# toyotune_3s.net
KiCad netlist of a schematic drawn in EAGLE
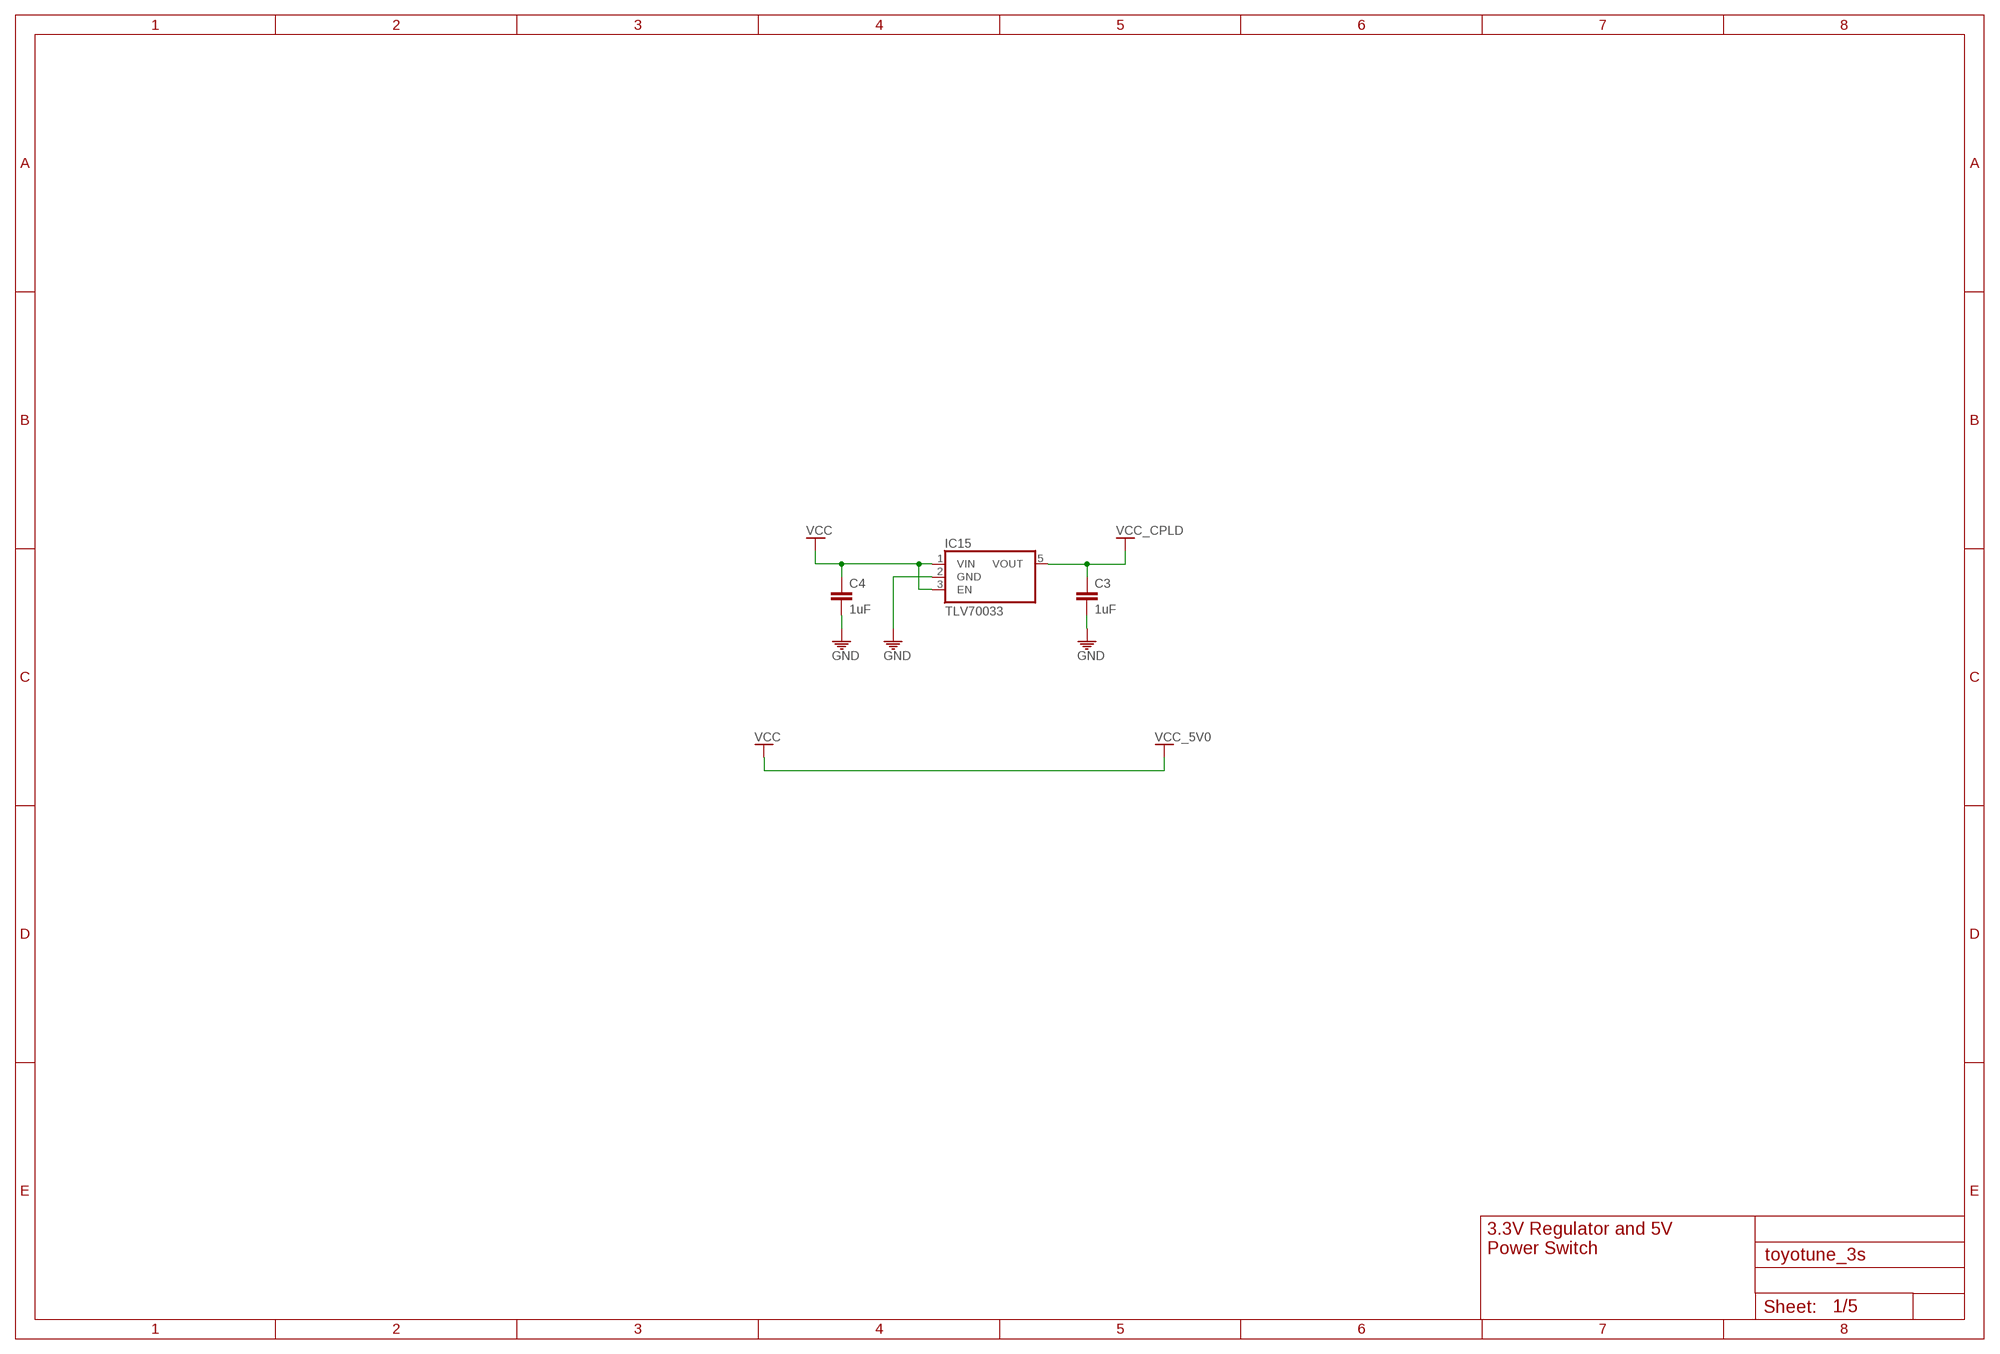
[diagram p0: schematic, sheet 1]
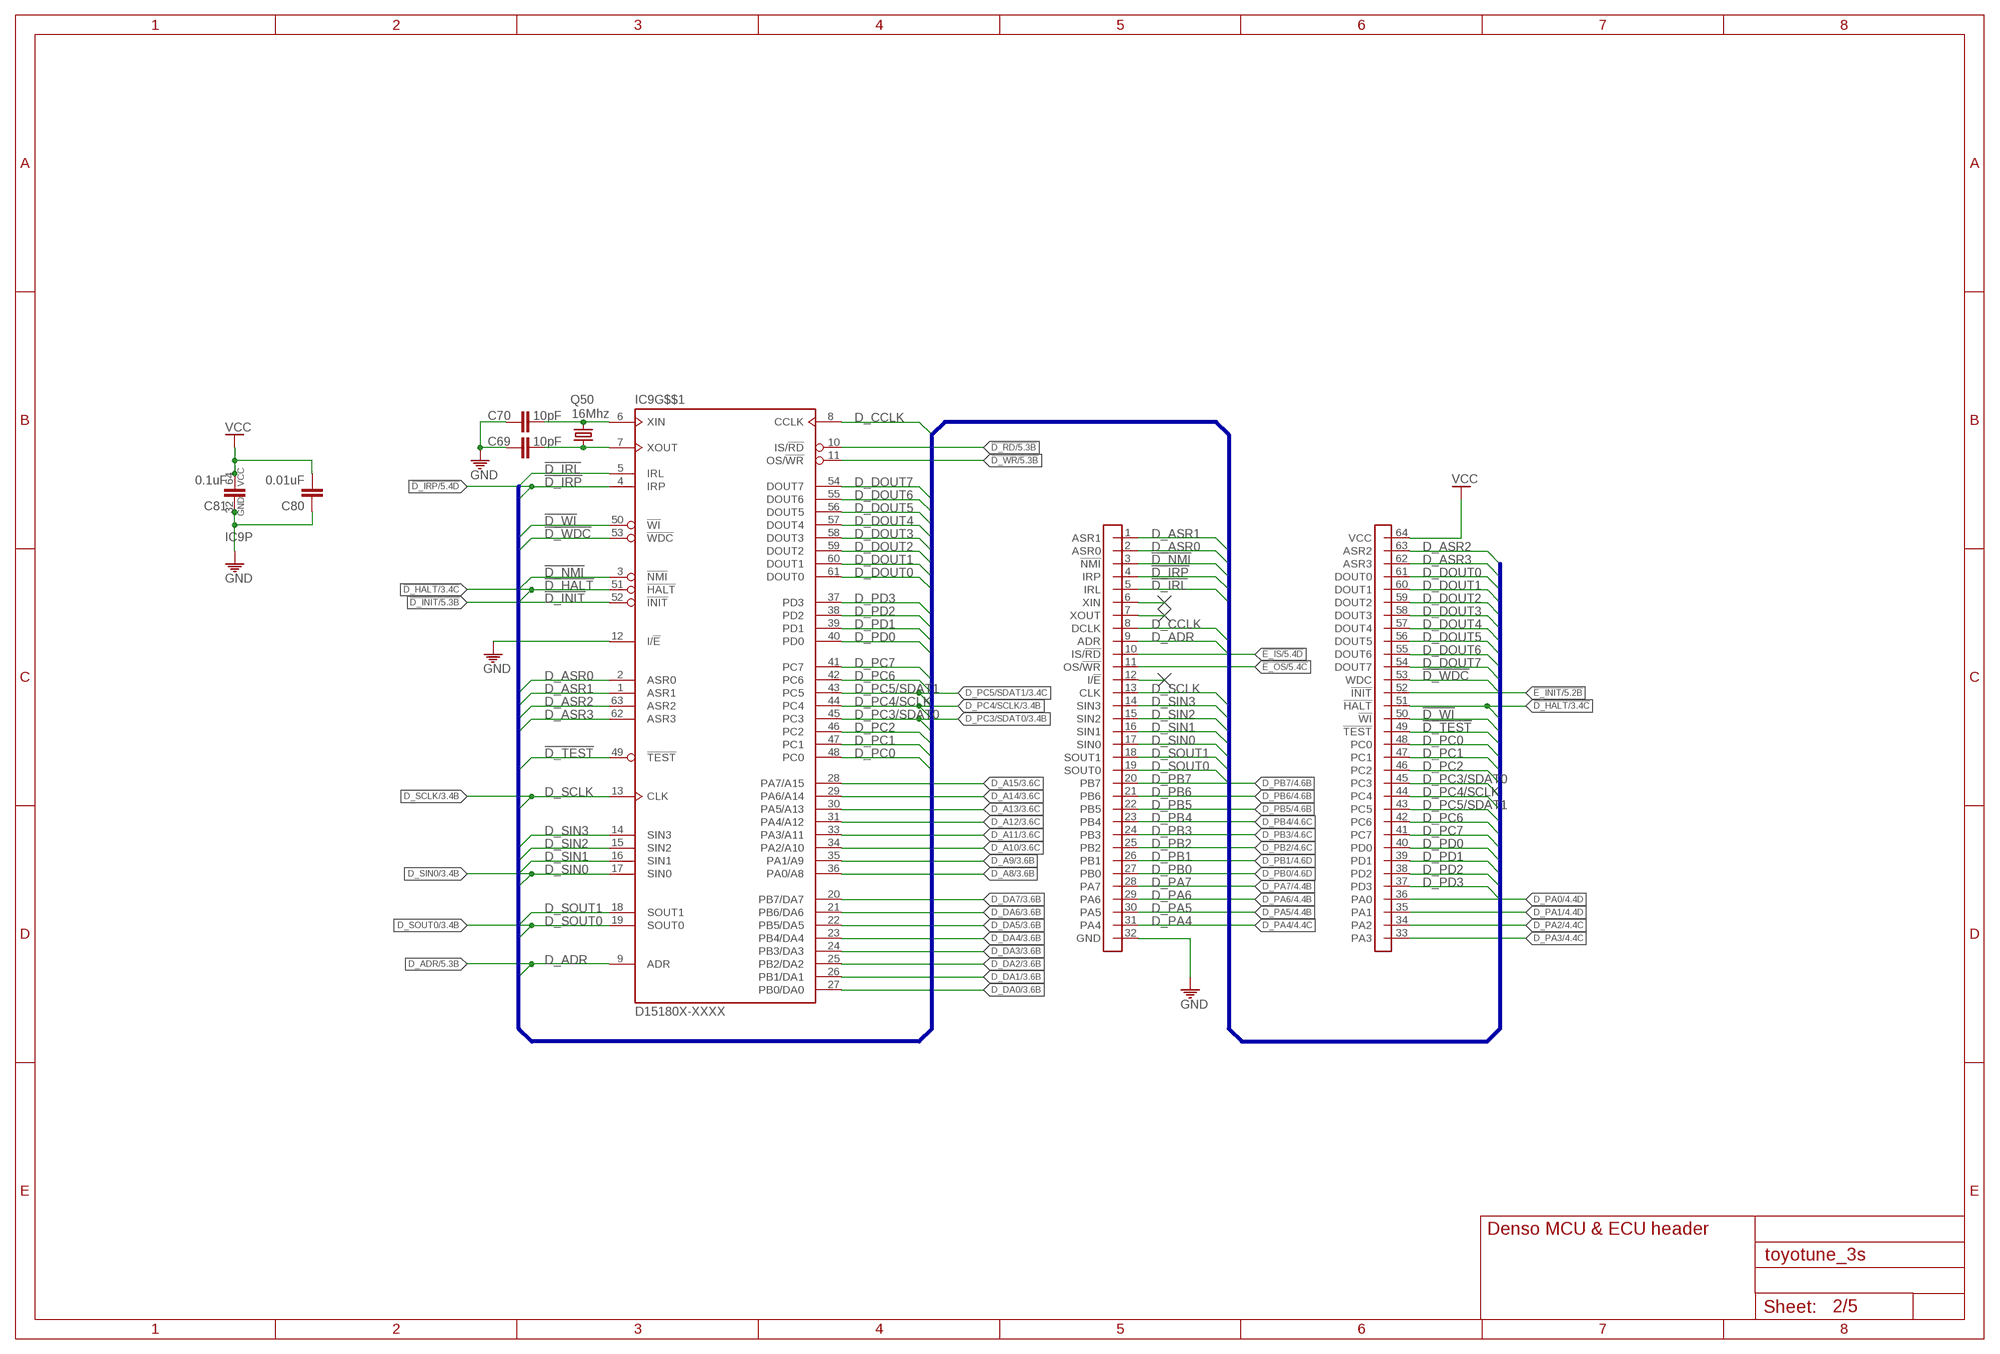
[diagram p1: schematic, sheet 2]
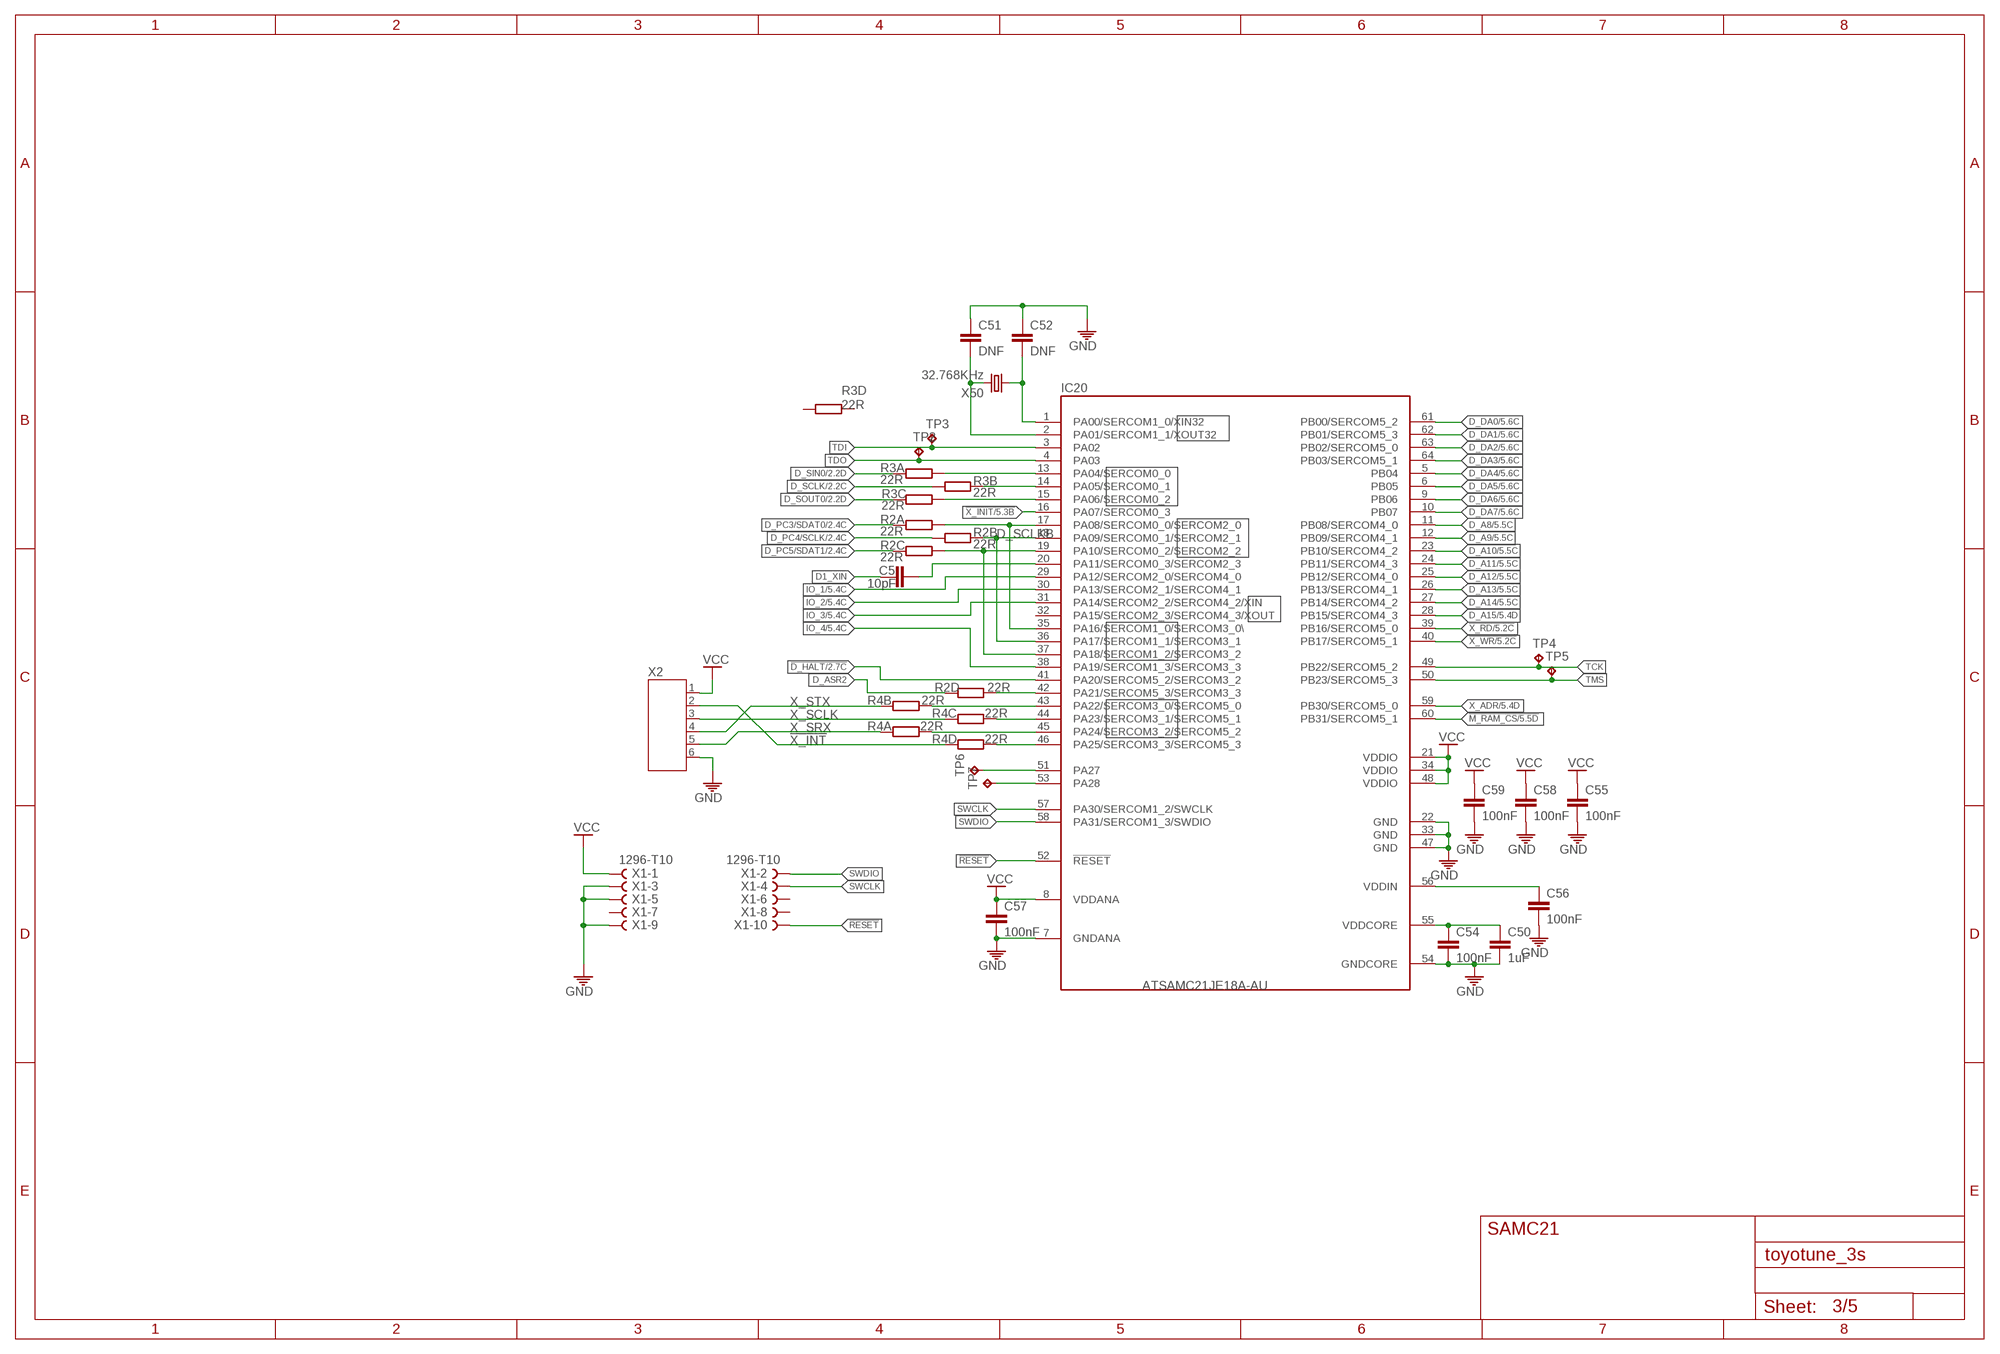
[diagram p2: schematic, sheet 3]
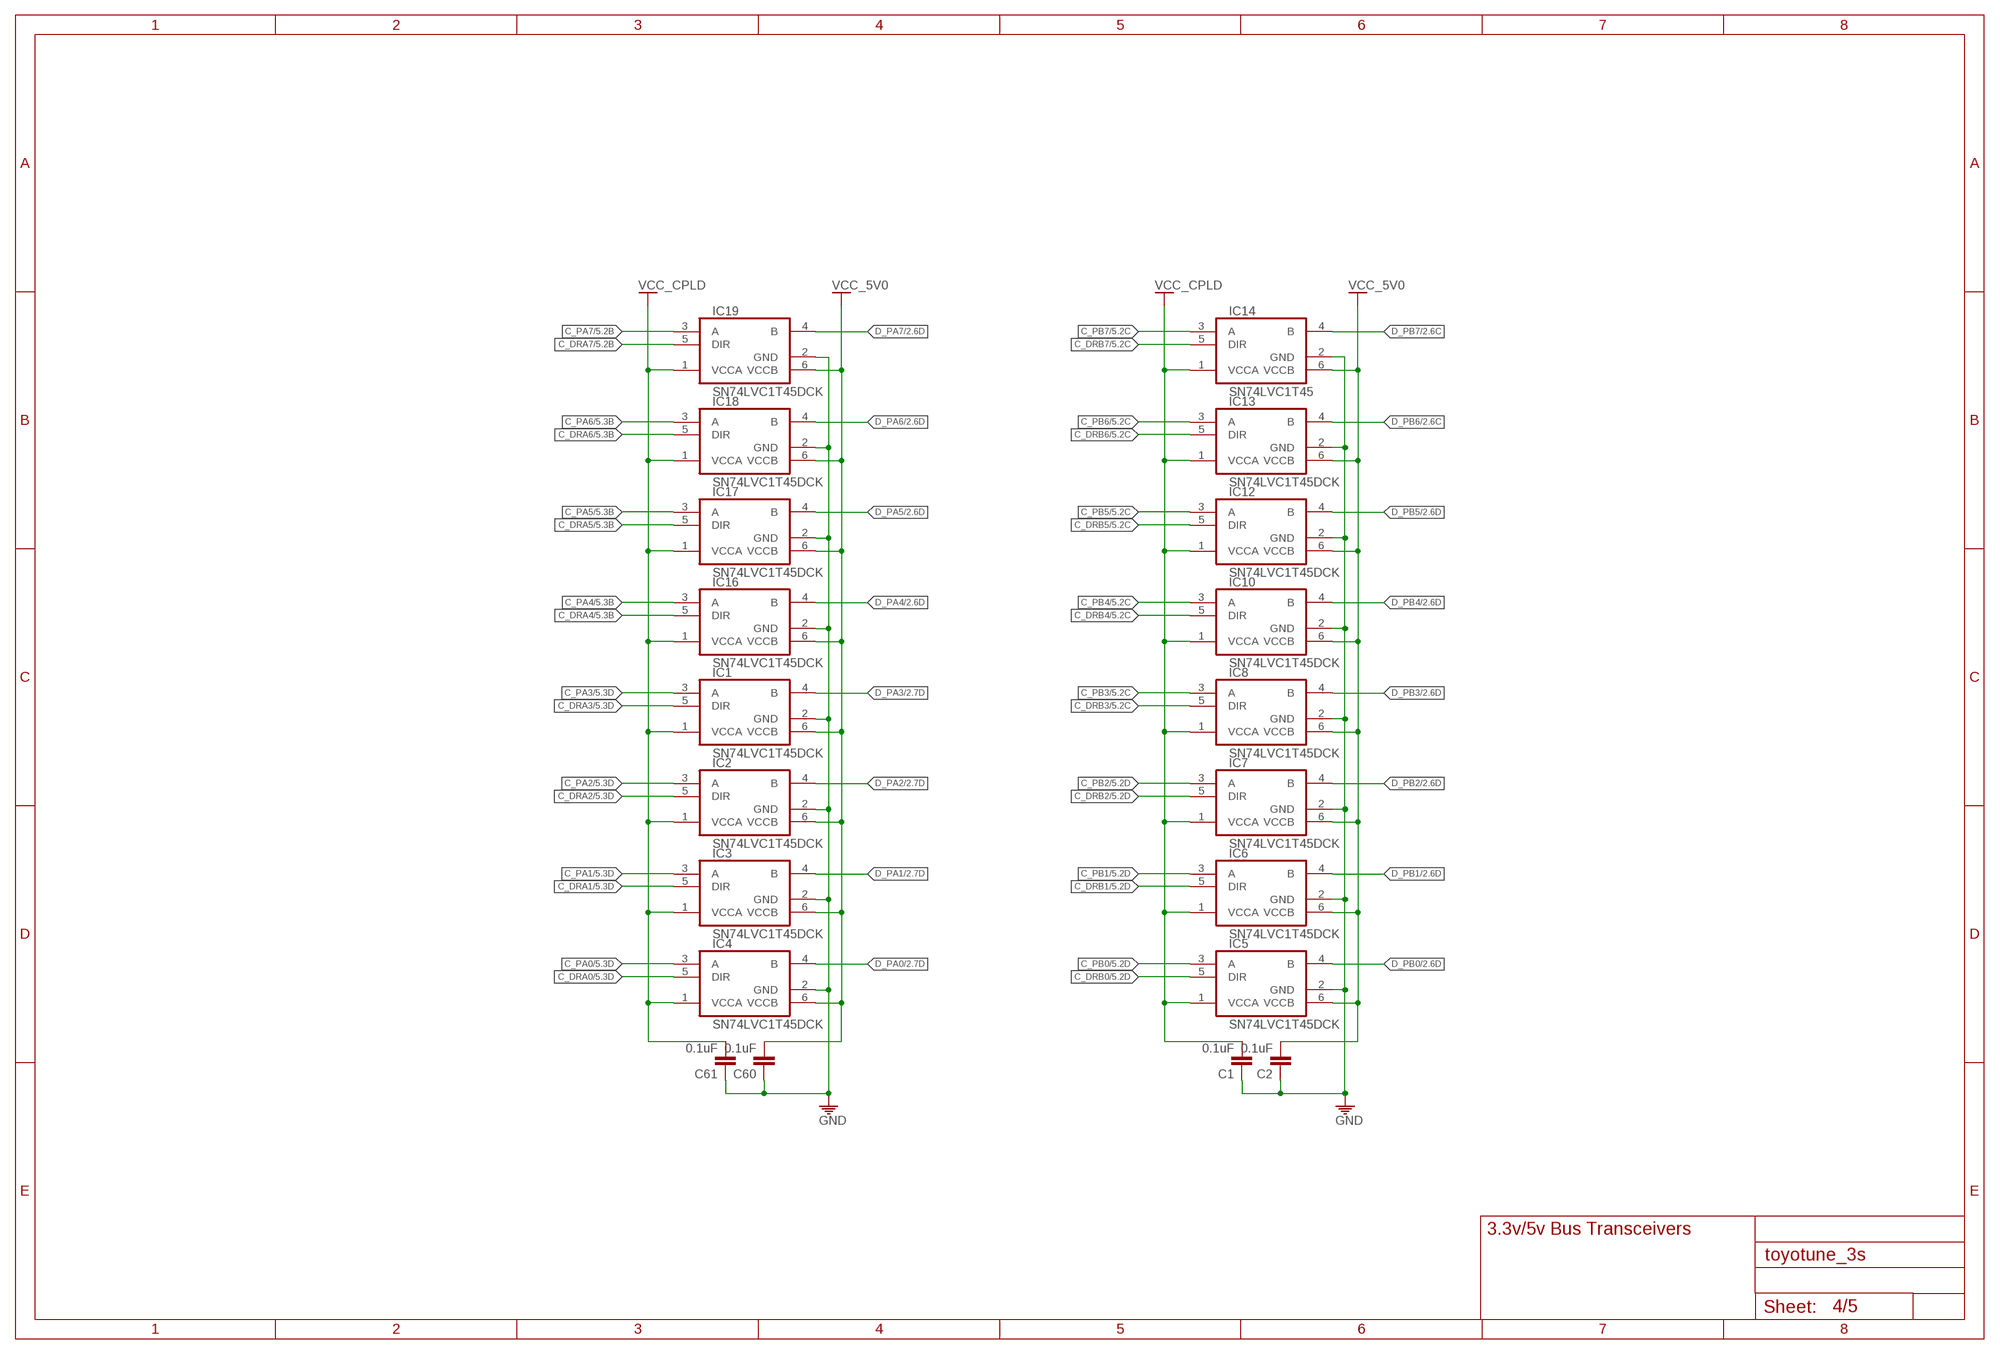
[diagram p3: schematic, sheet 4]
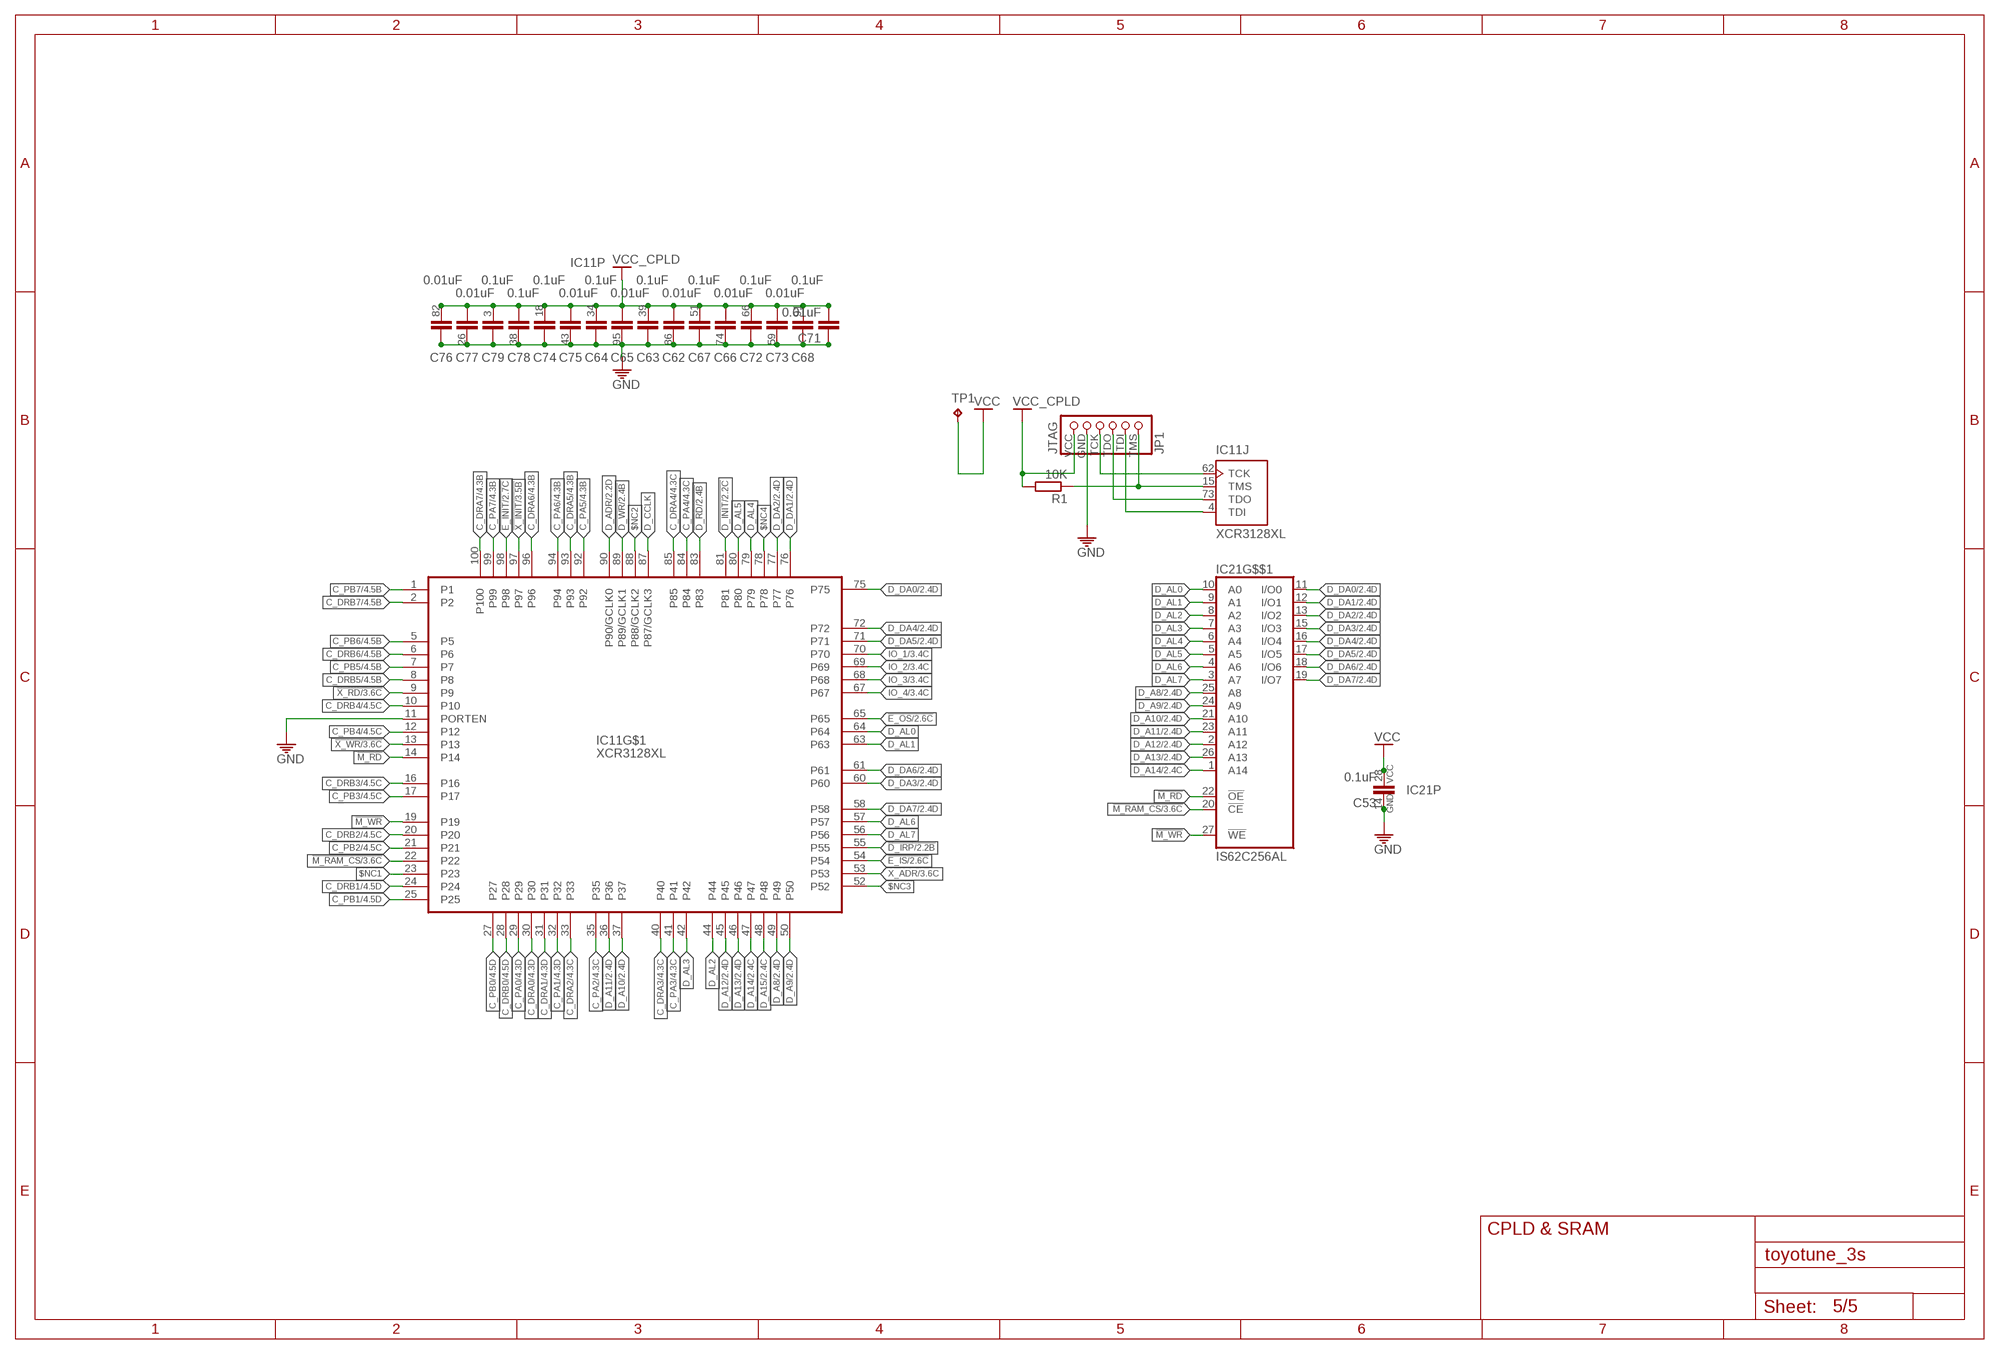
[diagram p4: schematic, sheet 5]

(export (version "E")
  (design (tool "Eeschema 10.0.6"))
  (components
    (comp (ref "C53")
      (value "0.1uF")
      (footprint "eagle-import:C0603")
      (libsource (lib "eagle-import") (part "C-EUC0603"))
    )
    (comp (ref "C62")
      (value "0.01uF")
      (footprint "eagle-import:C0603")
      (libsource (lib "eagle-import") (part "C-EUC0603"))
    )
    (comp (ref "C63")
      (value "0.1uF")
      (footprint "eagle-import:C0603")
      (libsource (lib "eagle-import") (part "C-EUC0603"))
    )
    (comp (ref "C64")
      (value "0.1uF")
      (footprint "eagle-import:C0603")
      (libsource (lib "eagle-import") (part "C-EUC0603"))
    )
    (comp (ref "C65")
      (value "0.01uF")
      (footprint "eagle-import:C0603")
      (libsource (lib "eagle-import") (part "C-EUC0603"))
    )
    (comp (ref "C66")
      (value "0.01uF")
      (footprint "eagle-import:C0603")
      (libsource (lib "eagle-import") (part "C-EUC0603"))
    )
    (comp (ref "C67")
      (value "0.1uF")
      (footprint "eagle-import:C0603")
      (libsource (lib "eagle-import") (part "C-EUC0603"))
    )
    (comp (ref "C68")
      (value "0.1uF")
      (footprint "eagle-import:C0603")
      (libsource (lib "eagle-import") (part "C-EUC0603"))
    )
    (comp (ref "C71")
      (value "0.01uF")
      (footprint "eagle-import:C0603")
      (libsource (lib "eagle-import") (part "C-EUC0603"))
    )
    (comp (ref "C72")
      (value "0.1uF")
      (footprint "eagle-import:C0603")
      (libsource (lib "eagle-import") (part "C-EUC0603"))
    )
    (comp (ref "C73")
      (value "0.01uF")
      (footprint "eagle-import:C0603")
      (libsource (lib "eagle-import") (part "C-EUC0603"))
    )
    (comp (ref "C74")
      (value "0.1uF")
      (footprint "eagle-import:C0603")
      (libsource (lib "eagle-import") (part "C-EUC0603"))
    )
    (comp (ref "C75")
      (value "0.01uF")
      (footprint "eagle-import:C0603")
      (libsource (lib "eagle-import") (part "C-EUC0603"))
    )
    (comp (ref "C76")
      (value "0.01uF")
      (footprint "eagle-import:C0603")
      (libsource (lib "eagle-import") (part "C-EUC0603"))
    )
    (comp (ref "C77")
      (value "0.01uF")
      (footprint "eagle-import:C0603")
      (libsource (lib "eagle-import") (part "C-EUC0603"))
    )
    (comp (ref "C78")
      (value "0.1uF")
      (footprint "eagle-import:C0603")
      (libsource (lib "eagle-import") (part "C-EUC0603"))
    )
    (comp (ref "C79")
      (value "0.1uF")
      (footprint "eagle-import:C0603")
      (libsource (lib "eagle-import") (part "C-EUC0603"))
    )
    (comp (ref "IC11")
      (value "XCR3128XL")
      (footprint "eagle-import:VQ100")
      (libsource (lib "eagle-import") (part "XCR3128XL"))
    )
    (comp (ref "IC21")
      (value "IS62C256AL")
      (footprint "eagle-import:TSOP28")
      (libsource (lib "eagle-import") (part "IS62C256AL"))
    )
    (comp (ref "JP1")
      (value "JTAG")
      (footprint "eagle-import:1X06_SMD")
      (libsource (lib "eagle-import") (part "JTAG_HEADERS"))
    )
    (comp (ref "R1")
      (value "10K")
      (footprint "eagle-import:R0603")
      (libsource (lib "eagle-import") (part "R-EU_R0603"))
    )
    (comp (ref "TP1")
      (value "TPTP13R")
      (footprint "eagle-import:TP13R")
      (libsource (lib "eagle-import") (part "TPTP13R"))
    )
    (comp (ref "C69")
      (value "10pF")
      (footprint "eagle-import:C0603")
      (libsource (lib "eagle-import") (part "C-EUC0603"))
    )
    (comp (ref "C70")
      (value "10pF")
      (footprint "eagle-import:C0603")
      (libsource (lib "eagle-import") (part "C-EUC0603"))
    )
    (comp (ref "C80")
      (value "0.01uF")
      (footprint "eagle-import:C0603")
      (libsource (lib "eagle-import") (part "C-EUC0603"))
    )
    (comp (ref "C81")
      (value "0.1uF")
      (footprint "eagle-import:C0603")
      (libsource (lib "eagle-import") (part "C-EUC0603"))
    )
    (comp (ref "IC9")
      (value "D15180X-XXXX")
      (footprint "eagle-import:SDIP-64")
      (libsource (lib "eagle-import") (part "D151803-9661"))
    )
    (comp (ref "Q50")
      (value "16Mhz")
      (footprint "eagle-import:CRYSTAL-SMD-5X3")
      (libsource (lib "eagle-import") (part "CRYSTAL5X3"))
    )
    (comp (ref "U1")
      (value "D151803-CONN")
      (footprint "eagle-import:SDIP-64-CONN")
      (libsource (lib "eagle-import") (part "D151803-CONN"))
    )
    (comp (ref "C3")
      (value "1uF")
      (footprint "eagle-import:C0603")
      (libsource (lib "eagle-import") (part "C-EUC0603"))
    )
    (comp (ref "C4")
      (value "1uF")
      (footprint "eagle-import:C0603")
      (libsource (lib "eagle-import") (part "C-EUC0603"))
    )
    (comp (ref "IC15")
      (value "TLV70033")
      (footprint "eagle-import:DDC_R-PDSO-G5")
      (libsource (lib "eagle-import") (part "TLV70033"))
    )
    (comp (ref "C5")
      (value "10pF")
      (footprint "eagle-import:C0603")
      (libsource (lib "eagle-import") (part "C-EUC0603"))
    )
    (comp (ref "C50")
      (value "1uF")
      (footprint "eagle-import:C0603")
      (libsource (lib "eagle-import") (part "C-EUC0603"))
    )
    (comp (ref "C51")
      (value "DNF")
      (footprint "eagle-import:C0603")
      (libsource (lib "eagle-import") (part "C-EUC0603"))
    )
    (comp (ref "C52")
      (value "DNF")
      (footprint "eagle-import:C0603")
      (libsource (lib "eagle-import") (part "C-EUC0603"))
    )
    (comp (ref "C54")
      (value "100nF")
      (footprint "eagle-import:C0603")
      (libsource (lib "eagle-import") (part "C-EUC0603"))
    )
    (comp (ref "C55")
      (value "100nF")
      (footprint "eagle-import:C0603")
      (libsource (lib "eagle-import") (part "C-EUC0603"))
    )
    (comp (ref "C56")
      (value "100nF")
      (footprint "eagle-import:C0603")
      (libsource (lib "eagle-import") (part "C-EUC0603"))
    )
    (comp (ref "C57")
      (value "100nF")
      (footprint "eagle-import:C0603")
      (libsource (lib "eagle-import") (part "C-EUC0603"))
    )
    (comp (ref "C58")
      (value "100nF")
      (footprint "eagle-import:C0603")
      (libsource (lib "eagle-import") (part "C-EUC0603"))
    )
    (comp (ref "C59")
      (value "100nF")
      (footprint "eagle-import:C0603")
      (libsource (lib "eagle-import") (part "C-EUC0603"))
    )
    (comp (ref "IC20")
      (value "ATSAMC21JE18A-AU")
      (footprint "eagle-import:TQFP64-05")
      (libsource (lib "eagle-import") (part "ATSAMC21JE18A-AU"))
    )
    (comp (ref "R2")
      (value "22R")
      (footprint "eagle-import:CAT16-J4")
      (libsource (lib "eagle-import") (part "CAT16-J4"))
    )
    (comp (ref "R3")
      (value "22R")
      (footprint "eagle-import:CAT16-J4")
      (libsource (lib "eagle-import") (part "CAT16-J4"))
    )
    (comp (ref "R4")
      (value "22R")
      (footprint "eagle-import:CAT16-J4")
      (libsource (lib "eagle-import") (part "CAT16-J4"))
    )
    (comp (ref "TP2")
      (value "TPTP08R")
      (footprint "eagle-import:TP08R")
      (libsource (lib "eagle-import") (part "TPTP08R"))
    )
    (comp (ref "TP3")
      (value "TPTP08R")
      (footprint "eagle-import:TP08R")
      (libsource (lib "eagle-import") (part "TPTP08R"))
    )
    (comp (ref "TP4")
      (value "TPTP08R")
      (footprint "eagle-import:TP08R")
      (libsource (lib "eagle-import") (part "TPTP08R"))
    )
    (comp (ref "TP5")
      (value "TPTP08R")
      (footprint "eagle-import:TP08R")
      (libsource (lib "eagle-import") (part "TPTP08R"))
    )
    (comp (ref "TP6")
      (value "TPTP08R")
      (footprint "eagle-import:TP08R")
      (libsource (lib "eagle-import") (part "TPTP08R"))
    )
    (comp (ref "TP7")
      (value "TPTP08R")
      (footprint "eagle-import:TP08R")
      (libsource (lib "eagle-import") (part "TPTP08R"))
    )
    (comp (ref "X1")
      (value "1296-T10")
      (footprint "eagle-import:1296-10")
      (libsource (lib "eagle-import") (part "1296-T10"))
    )
    (comp (ref "X2")
      (value "JST-PH6")
      (footprint "eagle-import:JST-PH6")
      (libsource (lib "eagle-import") (part "JST-PH6"))
    )
    (comp (ref "X50")
      (value "32.768KHz")
      (footprint "eagle-import:3.2X1.5-2-PAD")
      (libsource (lib "eagle-import") (part "CRYSTALS-NOGND-CFPX-217"))
    )
    (comp (ref "C1")
      (value "0.1uF")
      (footprint "eagle-import:C0603")
      (libsource (lib "eagle-import") (part "C-EUC0603"))
    )
    (comp (ref "C2")
      (value "0.1uF")
      (footprint "eagle-import:C0603")
      (libsource (lib "eagle-import") (part "C-EUC0603"))
    )
    (comp (ref "C60")
      (value "0.1uF")
      (footprint "eagle-import:C0603")
      (libsource (lib "eagle-import") (part "C-EUC0603"))
    )
    (comp (ref "C61")
      (value "0.1uF")
      (footprint "eagle-import:C0603")
      (libsource (lib "eagle-import") (part "C-EUC0603"))
    )
    (comp (ref "IC1")
      (value "SN74LVC1T45DCK")
      (footprint "eagle-import:DCK_R-PDSO-G6")
      (libsource (lib "eagle-import") (part "SN74LVC1T45DCK"))
    )
    (comp (ref "IC2")
      (value "SN74LVC1T45DCK")
      (footprint "eagle-import:DCK_R-PDSO-G6")
      (libsource (lib "eagle-import") (part "SN74LVC1T45DCK"))
    )
    (comp (ref "IC3")
      (value "SN74LVC1T45DCK")
      (footprint "eagle-import:DCK_R-PDSO-G6")
      (libsource (lib "eagle-import") (part "SN74LVC1T45DCK"))
    )
    (comp (ref "IC4")
      (value "SN74LVC1T45DCK")
      (footprint "eagle-import:DCK_R-PDSO-G6")
      (libsource (lib "eagle-import") (part "SN74LVC1T45DCK"))
    )
    (comp (ref "IC5")
      (value "SN74LVC1T45DCK")
      (footprint "eagle-import:DCK_R-PDSO-G6")
      (libsource (lib "eagle-import") (part "SN74LVC1T45DCK"))
    )
    (comp (ref "IC6")
      (value "SN74LVC1T45DCK")
      (footprint "eagle-import:DCK_R-PDSO-G6")
      (libsource (lib "eagle-import") (part "SN74LVC1T45DCK"))
    )
    (comp (ref "IC7")
      (value "SN74LVC1T45DCK")
      (footprint "eagle-import:DCK_R-PDSO-G6")
      (libsource (lib "eagle-import") (part "SN74LVC1T45DCK"))
    )
    (comp (ref "IC8")
      (value "SN74LVC1T45DCK")
      (footprint "eagle-import:DCK_R-PDSO-G6")
      (libsource (lib "eagle-import") (part "SN74LVC1T45DCK"))
    )
    (comp (ref "IC10")
      (value "SN74LVC1T45DCK")
      (footprint "eagle-import:DCK_R-PDSO-G6")
      (libsource (lib "eagle-import") (part "SN74LVC1T45DCK"))
    )
    (comp (ref "IC12")
      (value "SN74LVC1T45DCK")
      (footprint "eagle-import:DCK_R-PDSO-G6")
      (libsource (lib "eagle-import") (part "SN74LVC1T45DCK"))
    )
    (comp (ref "IC13")
      (value "SN74LVC1T45DCK")
      (footprint "eagle-import:DCK_R-PDSO-G6")
      (libsource (lib "eagle-import") (part "SN74LVC1T45DCK"))
    )
    (comp (ref "IC14")
      (value "SN74LVC1T45")
      (footprint "eagle-import:DCK_R-PDSO-G6")
      (libsource (lib "eagle-import") (part "SN74LVC1T45DCK"))
    )
    (comp (ref "IC16")
      (value "SN74LVC1T45DCK")
      (footprint "eagle-import:DCK_R-PDSO-G6")
      (libsource (lib "eagle-import") (part "SN74LVC1T45DCK"))
    )
    (comp (ref "IC17")
      (value "SN74LVC1T45DCK")
      (footprint "eagle-import:DCK_R-PDSO-G6")
      (libsource (lib "eagle-import") (part "SN74LVC1T45DCK"))
    )
    (comp (ref "IC18")
      (value "SN74LVC1T45DCK")
      (footprint "eagle-import:DCK_R-PDSO-G6")
      (libsource (lib "eagle-import") (part "SN74LVC1T45DCK"))
    )
    (comp (ref "IC19")
      (value "SN74LVC1T45DCK")
      (footprint "eagle-import:DCK_R-PDSO-G6")
      (libsource (lib "eagle-import") (part "SN74LVC1T45DCK"))
    )
  )
  (nets
    (net (code "1") (name "$NC1") (class "Default")
      (node (ref "IC11") (pin "23") (pinfunction "P23_23") (pintype "bidirectional"))
    )
    (net (code "2") (name "$NC2") (class "Default")
      (node (ref "IC11") (pin "88") (pinfunction "P88/GCLK2_88") (pintype "input"))
    )
    (net (code "3") (name "$NC3") (class "Default")
      (node (ref "IC11") (pin "52") (pinfunction "P52_52") (pintype "bidirectional"))
    )
    (net (code "4") (name "$NC4") (class "Default")
      (node (ref "IC11") (pin "78") (pinfunction "P78_78") (pintype "bidirectional"))
    )
    (net (code "5") (name "C_DRA0") (class "Default")
      (node (ref "IC11") (pin "30") (pinfunction "P30_30") (pintype "bidirectional"))
      (node (ref "IC4") (pin "5") (pinfunction "DIR_5") (pintype "input"))
    )
    (net (code "6") (name "C_DRA1") (class "Default")
      (node (ref "IC11") (pin "31") (pinfunction "P31_31") (pintype "bidirectional"))
      (node (ref "IC3") (pin "5") (pinfunction "DIR_5") (pintype "input"))
    )
    (net (code "7") (name "C_DRA2") (class "Default")
      (node (ref "IC11") (pin "33") (pinfunction "P33_33") (pintype "bidirectional"))
      (node (ref "IC2") (pin "5") (pinfunction "DIR_5") (pintype "input"))
    )
    (net (code "8") (name "C_DRA3") (class "Default")
      (node (ref "IC1") (pin "5") (pinfunction "DIR_5") (pintype "input"))
      (node (ref "IC11") (pin "40") (pinfunction "P40_40") (pintype "bidirectional"))
    )
    (net (code "9") (name "C_DRA4") (class "Default")
      (node (ref "IC11") (pin "85") (pinfunction "P85_85") (pintype "bidirectional"))
      (node (ref "IC16") (pin "5") (pinfunction "DIR_5") (pintype "input"))
    )
    (net (code "10") (name "C_DRA5") (class "Default")
      (node (ref "IC11") (pin "93") (pinfunction "P93_93") (pintype "bidirectional"))
      (node (ref "IC17") (pin "5") (pinfunction "DIR_5") (pintype "input"))
    )
    (net (code "11") (name "C_DRA6") (class "Default")
      (node (ref "IC11") (pin "96") (pinfunction "P96_96") (pintype "bidirectional"))
      (node (ref "IC18") (pin "5") (pinfunction "DIR_5") (pintype "input"))
    )
    (net (code "12") (name "C_DRA7") (class "Default")
      (node (ref "IC11") (pin "100") (pinfunction "P100_100") (pintype "bidirectional"))
      (node (ref "IC19") (pin "5") (pinfunction "DIR_5") (pintype "input"))
    )
    (net (code "13") (name "C_DRB0") (class "Default")
      (node (ref "IC11") (pin "28") (pinfunction "P28_28") (pintype "bidirectional"))
      (node (ref "IC5") (pin "5") (pinfunction "DIR_5") (pintype "input"))
    )
    (net (code "14") (name "C_DRB1") (class "Default")
      (node (ref "IC11") (pin "24") (pinfunction "P24_24") (pintype "bidirectional"))
      (node (ref "IC6") (pin "5") (pinfunction "DIR_5") (pintype "input"))
    )
    (net (code "15") (name "C_DRB2") (class "Default")
      (node (ref "IC11") (pin "20") (pinfunction "P20_20") (pintype "bidirectional"))
      (node (ref "IC7") (pin "5") (pinfunction "DIR_5") (pintype "input"))
    )
    (net (code "16") (name "C_DRB3") (class "Default")
      (node (ref "IC11") (pin "16") (pinfunction "P16_16") (pintype "bidirectional"))
      (node (ref "IC8") (pin "5") (pinfunction "DIR_5") (pintype "input"))
    )
    (net (code "17") (name "C_DRB4") (class "Default")
      (node (ref "IC10") (pin "5") (pinfunction "DIR_5") (pintype "input"))
      (node (ref "IC11") (pin "10") (pinfunction "P10_10") (pintype "bidirectional"))
    )
    (net (code "18") (name "C_DRB5") (class "Default")
      (node (ref "IC11") (pin "8") (pinfunction "P8_8") (pintype "bidirectional"))
      (node (ref "IC12") (pin "5") (pinfunction "DIR_5") (pintype "input"))
    )
    (net (code "19") (name "C_DRB6") (class "Default")
      (node (ref "IC11") (pin "6") (pinfunction "P6_6") (pintype "bidirectional"))
      (node (ref "IC13") (pin "5") (pinfunction "DIR_5") (pintype "input"))
    )
    (net (code "20") (name "C_DRB7") (class "Default")
      (node (ref "IC11") (pin "2") (pinfunction "P2_2") (pintype "bidirectional"))
      (node (ref "IC14") (pin "5") (pinfunction "DIR_5") (pintype "input"))
    )
    (net (code "21") (name "C_PA0") (class "Default")
      (node (ref "IC11") (pin "29") (pinfunction "P29_29") (pintype "bidirectional"))
      (node (ref "IC4") (pin "3") (pinfunction "A_3") (pintype "bidirectional"))
    )
    (net (code "22") (name "C_PA1") (class "Default")
      (node (ref "IC11") (pin "32") (pinfunction "P32_32") (pintype "bidirectional"))
      (node (ref "IC3") (pin "3") (pinfunction "A_3") (pintype "bidirectional"))
    )
    (net (code "23") (name "C_PA2") (class "Default")
      (node (ref "IC11") (pin "35") (pinfunction "P35_35") (pintype "bidirectional"))
      (node (ref "IC2") (pin "3") (pinfunction "A_3") (pintype "bidirectional"))
    )
    (net (code "24") (name "C_PA3") (class "Default")
      (node (ref "IC1") (pin "3") (pinfunction "A_3") (pintype "bidirectional"))
      (node (ref "IC11") (pin "41") (pinfunction "P41_41") (pintype "bidirectional"))
    )
    (net (code "25") (name "C_PA4") (class "Default")
      (node (ref "IC11") (pin "84") (pinfunction "P84_84") (pintype "bidirectional"))
      (node (ref "IC16") (pin "3") (pinfunction "A_3") (pintype "bidirectional"))
    )
    (net (code "26") (name "C_PA5") (class "Default")
      (node (ref "IC11") (pin "92") (pinfunction "P92_92") (pintype "bidirectional"))
      (node (ref "IC17") (pin "3") (pinfunction "A_3") (pintype "bidirectional"))
    )
    (net (code "27") (name "C_PA6") (class "Default")
      (node (ref "IC11") (pin "94") (pinfunction "P94_94") (pintype "bidirectional"))
      (node (ref "IC18") (pin "3") (pinfunction "A_3") (pintype "bidirectional"))
    )
    (net (code "28") (name "C_PA7") (class "Default")
      (node (ref "IC11") (pin "99") (pinfunction "P99_99") (pintype "bidirectional"))
      (node (ref "IC19") (pin "3") (pinfunction "A_3") (pintype "bidirectional"))
    )
    (net (code "29") (name "C_PB0") (class "Default")
      (node (ref "IC11") (pin "27") (pinfunction "P27_27") (pintype "bidirectional"))
      (node (ref "IC5") (pin "3") (pinfunction "A_3") (pintype "bidirectional"))
    )
    (net (code "30") (name "C_PB1") (class "Default")
      (node (ref "IC11") (pin "25") (pinfunction "P25_25") (pintype "bidirectional"))
      (node (ref "IC6") (pin "3") (pinfunction "A_3") (pintype "bidirectional"))
    )
    (net (code "31") (name "C_PB2") (class "Default")
      (node (ref "IC11") (pin "21") (pinfunction "P21_21") (pintype "bidirectional"))
      (node (ref "IC7") (pin "3") (pinfunction "A_3") (pintype "bidirectional"))
    )
    (net (code "32") (name "C_PB3") (class "Default")
      (node (ref "IC11") (pin "17") (pinfunction "P17_17") (pintype "bidirectional"))
      (node (ref "IC8") (pin "3") (pinfunction "A_3") (pintype "bidirectional"))
    )
    (net (code "33") (name "C_PB4") (class "Default")
      (node (ref "IC10") (pin "3") (pinfunction "A_3") (pintype "bidirectional"))
      (node (ref "IC11") (pin "12") (pinfunction "P12_12") (pintype "bidirectional"))
    )
    (net (code "34") (name "C_PB5") (class "Default")
      (node (ref "IC11") (pin "7") (pinfunction "P7_7") (pintype "bidirectional"))
      (node (ref "IC12") (pin "3") (pinfunction "A_3") (pintype "bidirectional"))
    )
    (net (code "35") (name "C_PB6") (class "Default")
      (node (ref "IC11") (pin "5") (pinfunction "P5_5") (pintype "bidirectional"))
      (node (ref "IC13") (pin "3") (pinfunction "A_3") (pintype "bidirectional"))
    )
    (net (code "36") (name "C_PB7") (class "Default")
      (node (ref "IC11") (pin "1") (pinfunction "P1_1") (pintype "bidirectional"))
      (node (ref "IC14") (pin "3") (pinfunction "A_3") (pintype "bidirectional"))
    )
    (net (code "37") (name "D1_XIN") (class "Default")
      (node (ref "C5") (pin "1") (pinfunction "1_1") (pintype "passive"))
      (node (ref "C70") (pin "2") (pinfunction "2_2") (pintype "passive"))
      (node (ref "IC9") (pin "6") (pinfunction "XIN_6") (pintype "bidirectional"))
      (node (ref "Q50") (pin "3") (pinfunction "2_3") (pintype "passive"))
    )
    (net (code "38") (name "D_A8") (class "Default")
      (node (ref "IC11") (pin "49") (pinfunction "P49_49") (pintype "bidirectional"))
      (node (ref "IC20") (pin "11") (pinfunction "PB08/SERCOM4_0_11") (pintype "bidirectional"))
      (node (ref "IC21") (pin "25") (pinfunction "A8_25") (pintype "input"))
      (node (ref "IC9") (pin "36") (pinfunction "PA0/A8_36") (pintype "bidirectional"))
    )
    (net (code "39") (name "D_A9") (class "Default")
      (node (ref "IC11") (pin "50") (pinfunction "P50_50") (pintype "bidirectional"))
      (node (ref "IC20") (pin "12") (pinfunction "PB09/SERCOM4_1_12") (pintype "bidirectional"))
      (node (ref "IC21") (pin "24") (pinfunction "A9_24") (pintype "input"))
      (node (ref "IC9") (pin "35") (pinfunction "PA1/A9_35") (pintype "bidirectional"))
    )
    (net (code "40") (name "D_A10") (class "Default")
      (node (ref "IC11") (pin "37") (pinfunction "P37_37") (pintype "bidirectional"))
      (node (ref "IC20") (pin "23") (pinfunction "PB10/SERCOM4_2_23") (pintype "bidirectional"))
      (node (ref "IC21") (pin "21") (pinfunction "A10_21") (pintype "input"))
      (node (ref "IC9") (pin "34") (pinfunction "PA2/A10_34") (pintype "bidirectional"))
    )
    (net (code "41") (name "D_A11") (class "Default")
      (node (ref "IC11") (pin "36") (pinfunction "P36_36") (pintype "bidirectional"))
      (node (ref "IC20") (pin "24") (pinfunction "PB11/SERCOM4_3_24") (pintype "bidirectional"))
      (node (ref "IC21") (pin "23") (pinfunction "A11_23") (pintype "input"))
      (node (ref "IC9") (pin "33") (pinfunction "PA3/A11_33") (pintype "bidirectional"))
    )
    (net (code "42") (name "D_A12") (class "Default")
      (node (ref "IC11") (pin "45") (pinfunction "P45_45") (pintype "bidirectional"))
      (node (ref "IC20") (pin "25") (pinfunction "PB12/SERCOM4_0_25") (pintype "bidirectional"))
      (node (ref "IC21") (pin "2") (pinfunction "A12_2") (pintype "input"))
      (node (ref "IC9") (pin "31") (pinfunction "PA4/A12_31") (pintype "bidirectional"))
    )
    (net (code "43") (name "D_A13") (class "Default")
      (node (ref "IC11") (pin "46") (pinfunction "P46_46") (pintype "bidirectional"))
      (node (ref "IC20") (pin "26") (pinfunction "PB13/SERCOM4_1_26") (pintype "bidirectional"))
      (node (ref "IC21") (pin "26") (pinfunction "A13_26") (pintype "input"))
      (node (ref "IC9") (pin "30") (pinfunction "PA5/A13_30") (pintype "bidirectional"))
    )
    (net (code "44") (name "D_A14") (class "Default")
      (node (ref "IC11") (pin "47") (pinfunction "P47_47") (pintype "bidirectional"))
      (node (ref "IC20") (pin "27") (pinfunction "PB14/SERCOM4_2_27") (pintype "bidirectional"))
      (node (ref "IC21") (pin "1") (pinfunction "A14_1") (pintype "input"))
      (node (ref "IC9") (pin "29") (pinfunction "PA6/A14_29") (pintype "bidirectional"))
    )
    (net (code "45") (name "D_A15") (class "Default")
      (node (ref "IC11") (pin "48") (pinfunction "P48_48") (pintype "bidirectional"))
      (node (ref "IC20") (pin "28") (pinfunction "PB15/SERCOM4_3_28") (pintype "bidirectional"))
      (node (ref "IC9") (pin "28") (pinfunction "PA7/A15_28") (pintype "bidirectional"))
    )
    (net (code "46") (name "D_ADR") (class "Default")
      (node (ref "IC11") (pin "90") (pinfunction "P90/GCLK0_90") (pintype "input"))
      (node (ref "IC9") (pin "9") (pinfunction "ADR_9") (pintype "output"))
      (node (ref "U1") (pin "9") (pinfunction "ADR_9") (pintype "bidirectional"))
    )
    (net (code "47") (name "D_AL0") (class "Default")
      (node (ref "IC11") (pin "64") (pinfunction "P64_64") (pintype "bidirectional"))
      (node (ref "IC21") (pin "10") (pinfunction "A0_10") (pintype "input"))
    )
    (net (code "48") (name "D_AL1") (class "Default")
      (node (ref "IC11") (pin "63") (pinfunction "P63_63") (pintype "bidirectional"))
      (node (ref "IC21") (pin "9") (pinfunction "A1_9") (pintype "input"))
    )
    (net (code "49") (name "D_AL2") (class "Default")
      (node (ref "IC11") (pin "44") (pinfunction "P44_44") (pintype "bidirectional"))
      (node (ref "IC21") (pin "8") (pinfunction "A2_8") (pintype "input"))
    )
    (net (code "50") (name "D_AL3") (class "Default")
      (node (ref "IC11") (pin "42") (pinfunction "P42_42") (pintype "bidirectional"))
      (node (ref "IC21") (pin "7") (pinfunction "A3_7") (pintype "input"))
    )
    (net (code "51") (name "D_AL4") (class "Default")
      (node (ref "IC11") (pin "79") (pinfunction "P79_79") (pintype "bidirectional"))
      (node (ref "IC21") (pin "6") (pinfunction "A4_6") (pintype "input"))
    )
    (net (code "52") (name "D_AL5") (class "Default")
      (node (ref "IC11") (pin "80") (pinfunction "P80_80") (pintype "bidirectional"))
      (node (ref "IC21") (pin "5") (pinfunction "A5_5") (pintype "input"))
    )
    (net (code "53") (name "D_AL6") (class "Default")
      (node (ref "IC11") (pin "57") (pinfunction "P57_57") (pintype "bidirectional"))
      (node (ref "IC21") (pin "4") (pinfunction "A6_4") (pintype "input"))
    )
    (net (code "54") (name "D_AL7") (class "Default")
      (node (ref "IC11") (pin "56") (pinfunction "P56_56") (pintype "bidirectional"))
      (node (ref "IC21") (pin "3") (pinfunction "A7_3") (pintype "input"))
    )
    (net (code "55") (name "D_ASR0") (class "Default")
      (node (ref "IC9") (pin "2") (pinfunction "ASR0_2") (pintype "input"))
      (node (ref "U1") (pin "2") (pinfunction "ASR0_2") (pintype "bidirectional"))
    )
    (net (code "56") (name "D_ASR1") (class "Default")
      (node (ref "IC9") (pin "1") (pinfunction "ASR1_1") (pintype "input"))
      (node (ref "U1") (pin "1") (pinfunction "ASR1_1") (pintype "bidirectional"))
    )
    (net (code "57") (name "D_ASR2") (class "Default")
      (node (ref "IC9") (pin "63") (pinfunction "ASR2_63") (pintype "input"))
      (node (ref "R2") (pin "4") (pinfunction "1_4") (pintype "passive"))
      (node (ref "U1") (pin "63") (pinfunction "ASR2_63") (pintype "bidirectional"))
    )
    (net (code "58") (name "D_ASR3") (class "Default")
      (node (ref "IC9") (pin "62") (pinfunction "ASR3_62") (pintype "input"))
      (node (ref "U1") (pin "62") (pinfunction "ASR3_62") (pintype "bidirectional"))
    )
    (net (code "59") (name "D_CCLK") (class "Default")
      (node (ref "IC11") (pin "87") (pinfunction "P87/GCLK3_87") (pintype "input"))
      (node (ref "IC9") (pin "8") (pinfunction "CCLK_8") (pintype "output"))
      (node (ref "U1") (pin "8") (pinfunction "DCLK_8") (pintype "bidirectional"))
    )
    (net (code "60") (name "D_DA0") (class "Default")
      (node (ref "IC11") (pin "75") (pinfunction "P75_75") (pintype "bidirectional"))
      (node (ref "IC20") (pin "61") (pinfunction "PB00/SERCOM5_2_61") (pintype "bidirectional"))
      (node (ref "IC21") (pin "11") (pinfunction "I/O0_11") (pintype "bidirectional"))
      (node (ref "IC9") (pin "27") (pinfunction "PB0/DA0_27") (pintype "bidirectional"))
    )
    (net (code "61") (name "D_DA1") (class "Default")
      (node (ref "IC11") (pin "76") (pinfunction "P76_76") (pintype "bidirectional"))
      (node (ref "IC20") (pin "62") (pinfunction "PB01/SERCOM5_3_62") (pintype "bidirectional"))
      (node (ref "IC21") (pin "12") (pinfunction "I/O1_12") (pintype "bidirectional"))
      (node (ref "IC9") (pin "26") (pinfunction "PB1/DA1_26") (pintype "bidirectional"))
    )
    (net (code "62") (name "D_DA2") (class "Default")
      (node (ref "IC11") (pin "77") (pinfunction "P77_77") (pintype "bidirectional"))
      (node (ref "IC20") (pin "63") (pinfunction "PB02/SERCOM5_0_63") (pintype "bidirectional"))
      (node (ref "IC21") (pin "13") (pinfunction "I/O2_13") (pintype "bidirectional"))
      (node (ref "IC9") (pin "25") (pinfunction "PB2/DA2_25") (pintype "bidirectional"))
    )
    (net (code "63") (name "D_DA3") (class "Default")
      (node (ref "IC11") (pin "60") (pinfunction "P60_60") (pintype "bidirectional"))
      (node (ref "IC20") (pin "64") (pinfunction "PB03/SERCOM5_1_64") (pintype "bidirectional"))
      (node (ref "IC21") (pin "15") (pinfunction "I/O3_15") (pintype "bidirectional"))
      (node (ref "IC9") (pin "24") (pinfunction "PB3/DA3_24") (pintype "bidirectional"))
    )
    (net (code "64") (name "D_DA4") (class "Default")
      (node (ref "IC11") (pin "72") (pinfunction "P72_72") (pintype "bidirectional"))
      (node (ref "IC20") (pin "5") (pinfunction "PB04_5") (pintype "bidirectional"))
      (node (ref "IC21") (pin "16") (pinfunction "I/O4_16") (pintype "bidirectional"))
      (node (ref "IC9") (pin "23") (pinfunction "PB4/DA4_23") (pintype "bidirectional"))
    )
    (net (code "65") (name "D_DA5") (class "Default")
      (node (ref "IC11") (pin "71") (pinfunction "P71_71") (pintype "bidirectional"))
      (node (ref "IC20") (pin "6") (pinfunction "PB05_6") (pintype "bidirectional"))
      (node (ref "IC21") (pin "17") (pinfunction "I/O5_17") (pintype "bidirectional"))
      (node (ref "IC9") (pin "22") (pinfunction "PB5/DA5_22") (pintype "bidirectional"))
    )
    (net (code "66") (name "D_DA6") (class "Default")
      (node (ref "IC11") (pin "61") (pinfunction "P61_61") (pintype "bidirectional"))
      (node (ref "IC20") (pin "9") (pinfunction "PB06_9") (pintype "bidirectional"))
      (node (ref "IC21") (pin "18") (pinfunction "I/O6_18") (pintype "bidirectional"))
      (node (ref "IC9") (pin "21") (pinfunction "PB6/DA6_21") (pintype "bidirectional"))
    )
    (net (code "67") (name "D_DA7") (class "Default")
      (node (ref "IC11") (pin "58") (pinfunction "P58_58") (pintype "bidirectional"))
      (node (ref "IC20") (pin "10") (pinfunction "PB07_10") (pintype "bidirectional"))
      (node (ref "IC21") (pin "19") (pinfunction "I/O7_19") (pintype "bidirectional"))
      (node (ref "IC9") (pin "20") (pinfunction "PB7/DA7_20") (pintype "bidirectional"))
    )
    (net (code "68") (name "D_DOUT0") (class "Default")
      (node (ref "IC9") (pin "61") (pinfunction "DOUT0_61") (pintype "bidirectional"))
      (node (ref "U1") (pin "61") (pinfunction "DOUT0_61") (pintype "bidirectional"))
    )
    (net (code "69") (name "D_DOUT1") (class "Default")
      (node (ref "IC9") (pin "60") (pinfunction "DOUT1_60") (pintype "bidirectional"))
      (node (ref "U1") (pin "60") (pinfunction "DOUT1_60") (pintype "bidirectional"))
    )
    (net (code "70") (name "D_DOUT2") (class "Default")
      (node (ref "IC9") (pin "59") (pinfunction "DOUT2_59") (pintype "bidirectional"))
      (node (ref "U1") (pin "59") (pinfunction "DOUT2_59") (pintype "bidirectional"))
    )
    (net (code "71") (name "D_DOUT3") (class "Default")
      (node (ref "IC9") (pin "58") (pinfunction "DOUT3_58") (pintype "bidirectional"))
      (node (ref "U1") (pin "58") (pinfunction "DOUT3_58") (pintype "bidirectional"))
    )
    (net (code "72") (name "D_DOUT4") (class "Default")
      (node (ref "IC9") (pin "57") (pinfunction "DOUT4_57") (pintype "bidirectional"))
      (node (ref "U1") (pin "57") (pinfunction "DOUT4_57") (pintype "bidirectional"))
    )
    (net (code "73") (name "D_DOUT5") (class "Default")
      (node (ref "IC9") (pin "56") (pinfunction "DOUT5_56") (pintype "bidirectional"))
      (node (ref "U1") (pin "56") (pinfunction "DOUT5_56") (pintype "bidirectional"))
    )
    (net (code "74") (name "D_DOUT6") (class "Default")
      (node (ref "IC9") (pin "55") (pinfunction "DOUT6_55") (pintype "bidirectional"))
      (node (ref "U1") (pin "55") (pinfunction "DOUT6_55") (pintype "bidirectional"))
    )
    (net (code "75") (name "D_DOUT7") (class "Default")
      (node (ref "IC9") (pin "54") (pinfunction "DOUT7_54") (pintype "bidirectional"))
      (node (ref "U1") (pin "54") (pinfunction "DOUT7_54") (pintype "bidirectional"))
    )
    (net (code "76") (name "D_PA0") (class "Default")
      (node (ref "IC4") (pin "4") (pinfunction "B_4") (pintype "bidirectional"))
      (node (ref "U1") (pin "36") (pinfunction "PA0_36") (pintype "bidirectional"))
    )
    (net (code "77") (name "D_PA1") (class "Default")
      (node (ref "IC3") (pin "4") (pinfunction "B_4") (pintype "bidirectional"))
      (node (ref "U1") (pin "35") (pinfunction "PA1_35") (pintype "bidirectional"))
    )
    (net (code "78") (name "D_PA2") (class "Default")
      (node (ref "IC2") (pin "4") (pinfunction "B_4") (pintype "bidirectional"))
      (node (ref "U1") (pin "34") (pinfunction "PA2_34") (pintype "bidirectional"))
    )
    (net (code "79") (name "D_PA3") (class "Default")
      (node (ref "IC1") (pin "4") (pinfunction "B_4") (pintype "bidirectional"))
      (node (ref "U1") (pin "33") (pinfunction "PA3_33") (pintype "bidirectional"))
    )
    (net (code "80") (name "D_PA4") (class "Default")
      (node (ref "IC16") (pin "4") (pinfunction "B_4") (pintype "bidirectional"))
      (node (ref "U1") (pin "31") (pinfunction "PA4_31") (pintype "bidirectional"))
    )
    (net (code "81") (name "D_PA5") (class "Default")
      (node (ref "IC17") (pin "4") (pinfunction "B_4") (pintype "bidirectional"))
      (node (ref "U1") (pin "30") (pinfunction "PA5_30") (pintype "bidirectional"))
    )
    (net (code "82") (name "D_PA6") (class "Default")
      (node (ref "IC18") (pin "4") (pinfunction "B_4") (pintype "bidirectional"))
      (node (ref "U1") (pin "29") (pinfunction "PA6_29") (pintype "bidirectional"))
    )
    (net (code "83") (name "D_PA7") (class "Default")
      (node (ref "IC19") (pin "4") (pinfunction "B_4") (pintype "bidirectional"))
      (node (ref "U1") (pin "28") (pinfunction "PA7_28") (pintype "bidirectional"))
    )
    (net (code "84") (name "D_PB0") (class "Default")
      (node (ref "IC5") (pin "4") (pinfunction "B_4") (pintype "bidirectional"))
      (node (ref "U1") (pin "27") (pinfunction "PB0_27") (pintype "bidirectional"))
    )
    (net (code "85") (name "D_PB1") (class "Default")
      (node (ref "IC6") (pin "4") (pinfunction "B_4") (pintype "bidirectional"))
      (node (ref "U1") (pin "26") (pinfunction "PB1_26") (pintype "bidirectional"))
    )
    (net (code "86") (name "D_PB2") (class "Default")
      (node (ref "IC7") (pin "4") (pinfunction "B_4") (pintype "bidirectional"))
      (node (ref "U1") (pin "25") (pinfunction "PB2_25") (pintype "bidirectional"))
    )
    (net (code "87") (name "D_PB3") (class "Default")
      (node (ref "IC8") (pin "4") (pinfunction "B_4") (pintype "bidirectional"))
      (node (ref "U1") (pin "24") (pinfunction "PB3_24") (pintype "bidirectional"))
    )
    (net (code "88") (name "D_PB4") (class "Default")
      (node (ref "IC10") (pin "4") (pinfunction "B_4") (pintype "bidirectional"))
      (node (ref "U1") (pin "23") (pinfunction "PB4_23") (pintype "bidirectional"))
    )
    (net (code "89") (name "D_PB5") (class "Default")
      (node (ref "IC12") (pin "4") (pinfunction "B_4") (pintype "bidirectional"))
      (node (ref "U1") (pin "22") (pinfunction "PB5_22") (pintype "bidirectional"))
    )
    (net (code "90") (name "D_PB6") (class "Default")
      (node (ref "IC13") (pin "4") (pinfunction "B_4") (pintype "bidirectional"))
      (node (ref "U1") (pin "21") (pinfunction "PB6_21") (pintype "bidirectional"))
    )
    (net (code "91") (name "D_PB7") (class "Default")
      (node (ref "IC14") (pin "4") (pinfunction "B_4") (pintype "bidirectional"))
      (node (ref "U1") (pin "20") (pinfunction "PB7_20") (pintype "bidirectional"))
    )
    (net (code "92") (name "D_PC0") (class "Default")
      (node (ref "IC9") (pin "48") (pinfunction "PC0_48") (pintype "bidirectional"))
      (node (ref "U1") (pin "48") (pinfunction "PC0_48") (pintype "bidirectional"))
    )
    (net (code "93") (name "D_PC1") (class "Default")
      (node (ref "IC9") (pin "47") (pinfunction "PC1_47") (pintype "bidirectional"))
      (node (ref "U1") (pin "47") (pinfunction "PC1_47") (pintype "bidirectional"))
    )
    (net (code "94") (name "D_PC2") (class "Default")
      (node (ref "IC9") (pin "46") (pinfunction "PC2_46") (pintype "bidirectional"))
      (node (ref "U1") (pin "46") (pinfunction "PC2_46") (pintype "bidirectional"))
    )
    (net (code "95") (name "D_PC3{slash}SDAT0") (class "Default")
      (node (ref "IC9") (pin "45") (pinfunction "PC3_45") (pintype "bidirectional"))
      (node (ref "R2") (pin "1") (pinfunction "1_1") (pintype "passive"))
      (node (ref "U1") (pin "45") (pinfunction "PC3_45") (pintype "bidirectional"))
    )
    (net (code "96") (name "D_PC4{slash}SCLK") (class "Default")
      (node (ref "IC9") (pin "44") (pinfunction "PC4_44") (pintype "bidirectional"))
      (node (ref "R2") (pin "2") (pinfunction "1_2") (pintype "passive"))
      (node (ref "U1") (pin "44") (pinfunction "PC4_44") (pintype "bidirectional"))
    )
    (net (code "97") (name "D_PC5{slash}SDAT1") (class "Default")
      (node (ref "IC9") (pin "43") (pinfunction "PC5_43") (pintype "bidirectional"))
      (node (ref "R2") (pin "3") (pinfunction "1_3") (pintype "passive"))
      (node (ref "U1") (pin "43") (pinfunction "PC5_43") (pintype "bidirectional"))
    )
    (net (code "98") (name "D_PC6") (class "Default")
      (node (ref "IC9") (pin "42") (pinfunction "PC6_42") (pintype "bidirectional"))
      (node (ref "U1") (pin "42") (pinfunction "PC6_42") (pintype "bidirectional"))
    )
    (net (code "99") (name "D_PC7") (class "Default")
      (node (ref "IC9") (pin "41") (pinfunction "PC7_41") (pintype "bidirectional"))
      (node (ref "U1") (pin "41") (pinfunction "PC7_41") (pintype "bidirectional"))
    )
    (net (code "100") (name "D_PD0") (class "Default")
      (node (ref "IC9") (pin "40") (pinfunction "PD0_40") (pintype "bidirectional"))
      (node (ref "U1") (pin "40") (pinfunction "PD0_40") (pintype "bidirectional"))
    )
    (net (code "101") (name "D_PD1") (class "Default")
      (node (ref "IC9") (pin "39") (pinfunction "PD1_39") (pintype "bidirectional"))
      (node (ref "U1") (pin "39") (pinfunction "PD1_39") (pintype "bidirectional"))
    )
    (net (code "102") (name "D_PD2") (class "Default")
      (node (ref "IC9") (pin "38") (pinfunction "PD2_38") (pintype "bidirectional"))
      (node (ref "U1") (pin "38") (pinfunction "PD2_38") (pintype "bidirectional"))
    )
    (net (code "103") (name "D_PD3") (class "Default")
      (node (ref "IC9") (pin "37") (pinfunction "PD3_37") (pintype "bidirectional"))
      (node (ref "U1") (pin "37") (pinfunction "PD3_37") (pintype "bidirectional"))
    )
    (net (code "104") (name "D_SCLK") (class "Default")
      (node (ref "IC9") (pin "13") (pinfunction "CLK_13") (pintype "output"))
      (node (ref "R3") (pin "2") (pinfunction "1_2") (pintype "passive"))
      (node (ref "U1") (pin "13") (pinfunction "CLK_13") (pintype "bidirectional"))
    )
    (net (code "105") (name "D_SCLKB") (class "Default")
      (node (ref "IC20") (pin "18") (pinfunction "PA09/SERCOM0_1/SERCOM2_1_18") (pintype "bidirectional"))
      (node (ref "IC20") (pin "36") (pinfunction "PA17/SERCOM1_1/SERCOM3_1_36") (pintype "bidirectional"))
      (node (ref "R2") (pin "7") (pinfunction "2_7") (pintype "passive"))
    )
    (net (code "106") (name "D_SIN0") (class "Default")
      (node (ref "IC9") (pin "17") (pinfunction "SIN0_17") (pintype "input"))
      (node (ref "R3") (pin "1") (pinfunction "1_1") (pintype "passive"))
      (node (ref "U1") (pin "17") (pinfunction "SIN0_17") (pintype "bidirectional"))
    )
    (net (code "107") (name "D_SIN1") (class "Default")
      (node (ref "IC9") (pin "16") (pinfunction "SIN1_16") (pintype "input"))
      (node (ref "U1") (pin "16") (pinfunction "SIN1_16") (pintype "bidirectional"))
    )
    (net (code "108") (name "D_SIN2") (class "Default")
      (node (ref "IC9") (pin "15") (pinfunction "SIN2_15") (pintype "input"))
      (node (ref "U1") (pin "15") (pinfunction "SIN2_15") (pintype "bidirectional"))
    )
    (net (code "109") (name "D_SIN3") (class "Default")
      (node (ref "IC9") (pin "14") (pinfunction "SIN3_14") (pintype "input"))
      (node (ref "U1") (pin "14") (pinfunction "SIN3_14") (pintype "bidirectional"))
    )
    (net (code "110") (name "D_SOUT0") (class "Default")
      (node (ref "IC9") (pin "19") (pinfunction "SOUT0_19") (pintype "output"))
      (node (ref "R3") (pin "3") (pinfunction "1_3") (pintype "passive"))
      (node (ref "U1") (pin "19") (pinfunction "SOUT0_19") (pintype "bidirectional"))
    )
    (net (code "111") (name "D_SOUT1") (class "Default")
      (node (ref "IC9") (pin "18") (pinfunction "SOUT1_18") (pintype "output"))
      (node (ref "U1") (pin "18") (pinfunction "SOUT1_18") (pintype "bidirectional"))
    )
    (net (code "112") (name "GND") (class "Default")
      (node (ref "C1") (pin "1") (pinfunction "1_1") (pintype "passive"))
      (node (ref "C2") (pin "1") (pinfunction "1_1") (pintype "passive"))
      (node (ref "C3") (pin "2") (pinfunction "2_2") (pintype "passive"))
      (node (ref "C4") (pin "2") (pinfunction "2_2") (pintype "passive"))
      (node (ref "C50") (pin "2") (pinfunction "2_2") (pintype "passive"))
      (node (ref "C51") (pin "1") (pinfunction "1_1") (pintype "passive"))
      (node (ref "C52") (pin "1") (pinfunction "1_1") (pintype "passive"))
      (node (ref "C53") (pin "1") (pinfunction "1_1") (pintype "passive"))
      (node (ref "C54") (pin "2") (pinfunction "2_2") (pintype "passive"))
      (node (ref "C55") (pin "2") (pinfunction "2_2") (pintype "passive"))
      (node (ref "C56") (pin "2") (pinfunction "2_2") (pintype "passive"))
      (node (ref "C57") (pin "2") (pinfunction "2_2") (pintype "passive"))
      (node (ref "C58") (pin "2") (pinfunction "2_2") (pintype "passive"))
      (node (ref "C59") (pin "2") (pinfunction "2_2") (pintype "passive"))
      (node (ref "C60") (pin "1") (pinfunction "1_1") (pintype "passive"))
      (node (ref "C61") (pin "1") (pinfunction "1_1") (pintype "passive"))
      (node (ref "C62") (pin "1") (pinfunction "1_1") (pintype "passive"))
      (node (ref "C63") (pin "1") (pinfunction "1_1") (pintype "passive"))
      (node (ref "C64") (pin "1") (pinfunction "1_1") (pintype "passive"))
      (node (ref "C65") (pin "1") (pinfunction "1_1") (pintype "passive"))
      (node (ref "C66") (pin "1") (pinfunction "1_1") (pintype "passive"))
      (node (ref "C67") (pin "1") (pinfunction "1_1") (pintype "passive"))
      (node (ref "C68") (pin "1") (pinfunction "1_1") (pintype "passive"))
      (node (ref "C69") (pin "2") (pinfunction "2_2") (pintype "passive"))
      (node (ref "C70") (pin "1") (pinfunction "1_1") (pintype "passive"))
      (node (ref "C71") (pin "1") (pinfunction "1_1") (pintype "passive"))
      (node (ref "C72") (pin "1") (pinfunction "1_1") (pintype "passive"))
      (node (ref "C73") (pin "1") (pinfunction "1_1") (pintype "passive"))
      (node (ref "C74") (pin "1") (pinfunction "1_1") (pintype "passive"))
      (node (ref "C75") (pin "1") (pinfunction "1_1") (pintype "passive"))
      (node (ref "C76") (pin "1") (pinfunction "1_1") (pintype "passive"))
      (node (ref "C77") (pin "1") (pinfunction "1_1") (pintype "passive"))
      (node (ref "C78") (pin "1") (pinfunction "1_1") (pintype "passive"))
      (node (ref "C79") (pin "1") (pinfunction "1_1") (pintype "passive"))
      (node (ref "C80") (pin "1") (pinfunction "1_1") (pintype "passive"))
      (node (ref "C81") (pin "1") (pinfunction "1_1") (pintype "passive"))
      (node (ref "IC1") (pin "2") (pinfunction "GND_2") (pintype "power_in"))
      (node (ref "IC10") (pin "2") (pinfunction "GND_2") (pintype "power_in"))
      (node (ref "IC11") (pin "11") (pinfunction "PORTEN_11") (pintype "bidirectional"))
      (node (ref "IC11") (pin "26") (pinfunction "GND_26") (pintype "power_in"))
      (node (ref "IC11") (pin "38") (pinfunction "GND_38") (pintype "power_in"))
      (node (ref "IC11") (pin "43") (pinfunction "GND_43") (pintype "power_in"))
      (node (ref "IC11") (pin "59") (pinfunction "GND_59") (pintype "power_in"))
      (node (ref "IC11") (pin "74") (pinfunction "GND_74") (pintype "power_in"))
      (node (ref "IC11") (pin "86") (pinfunction "GND_86") (pintype "power_in"))
      (node (ref "IC11") (pin "95") (pinfunction "GND_95") (pintype "power_in"))
      (node (ref "IC12") (pin "2") (pinfunction "GND_2") (pintype "power_in"))
      (node (ref "IC13") (pin "2") (pinfunction "GND_2") (pintype "power_in"))
      (node (ref "IC14") (pin "2") (pinfunction "GND_2") (pintype "power_in"))
      (node (ref "IC15") (pin "2") (pinfunction "GND_2") (pintype "power_in"))
      (node (ref "IC16") (pin "2") (pinfunction "GND_2") (pintype "power_in"))
      (node (ref "IC17") (pin "2") (pinfunction "GND_2") (pintype "power_in"))
      (node (ref "IC18") (pin "2") (pinfunction "GND_2") (pintype "power_in"))
      (node (ref "IC19") (pin "2") (pinfunction "GND_2") (pintype "power_in"))
      (node (ref "IC2") (pin "2") (pinfunction "GND_2") (pintype "power_in"))
      (node (ref "IC20") (pin "22") (pinfunction "GND_22") (pintype "power_in"))
      (node (ref "IC20") (pin "33") (pinfunction "GND_33") (pintype "power_in"))
      (node (ref "IC20") (pin "47") (pinfunction "GND_47") (pintype "power_in"))
      (node (ref "IC20") (pin "54") (pinfunction "GNDCORE_54") (pintype "power_in"))
      (node (ref "IC20") (pin "7") (pinfunction "GNDANA_7") (pintype "power_in"))
      (node (ref "IC21") (pin "14") (pinfunction "GND_14") (pintype "power_in"))
      (node (ref "IC3") (pin "2") (pinfunction "GND_2") (pintype "power_in"))
      (node (ref "IC4") (pin "2") (pinfunction "GND_2") (pintype "power_in"))
      (node (ref "IC5") (pin "2") (pinfunction "GND_2") (pintype "power_in"))
      (node (ref "IC6") (pin "2") (pinfunction "GND_2") (pintype "power_in"))
      (node (ref "IC7") (pin "2") (pinfunction "GND_2") (pintype "power_in"))
      (node (ref "IC8") (pin "2") (pinfunction "GND_2") (pintype "power_in"))
      (node (ref "IC9") (pin "12") (pinfunction "I/~{E}_12") (pintype "input"))
      (node (ref "IC9") (pin "32") (pinfunction "GND_32") (pintype "power_in"))
      (node (ref "JP1") (pin "GND") (pinfunction "5_GND") (pintype "passive"))
      (node (ref "U1") (pin "32") (pinfunction "GND_32") (pintype "bidirectional"))
      (node (ref "X1") (pin "3") (pinfunction "B_3") (pintype "passive"))
      (node (ref "X1") (pin "5") (pinfunction "B_5") (pintype "passive"))
      (node (ref "X1") (pin "9") (pinfunction "B_9") (pintype "passive"))
      (node (ref "X2") (pin "6") (pinfunction "6_6") (pintype "passive"))
    )
    (net (code "113") (name "IO_1") (class "Default")
      (node (ref "IC11") (pin "70") (pinfunction "P70_70") (pintype "bidirectional"))
      (node (ref "IC20") (pin "29") (pinfunction "PA12/SERCOM2_0/SERCOM4_0_29") (pintype "bidirectional"))
    )
    (net (code "114") (name "IO_2") (class "Default")
      (node (ref "IC11") (pin "69") (pinfunction "P69_69") (pintype "bidirectional"))
      (node (ref "IC20") (pin "30") (pinfunction "PA13/SERCOM2_1/SERCOM4_1_30") (pintype "bidirectional"))
    )
    (net (code "115") (name "IO_3") (class "Default")
      (node (ref "IC11") (pin "68") (pinfunction "P68_68") (pintype "bidirectional"))
      (node (ref "IC20") (pin "31") (pinfunction "PA14/SERCOM2_2/SERCOM4_2/XIN_31") (pintype "bidirectional"))
    )
    (net (code "116") (name "IO_4") (class "Default")
      (node (ref "IC11") (pin "67") (pinfunction "P67_67") (pintype "bidirectional"))
      (node (ref "IC20") (pin "38") (pinfunction "PA19/SERCOM1_3/SERCOM3_3_38") (pintype "bidirectional"))
    )
    (net (code "117") (name "Net-(IC9A-XOUT)") (class "Default")
      (node (ref "C69") (pin "1") (pinfunction "1_1") (pintype "passive"))
      (node (ref "IC9") (pin "7") (pinfunction "XOUT_7") (pintype "bidirectional"))
      (node (ref "Q50") (pin "1") (pinfunction "1_1") (pintype "passive"))
    )
    (net (code "118") (name "Net-(IC20-PA00{slash}SERCOM1_0{slash}XIN32)") (class "Default")
      (node (ref "C52") (pin "2") (pinfunction "2_2") (pintype "passive"))
      (node (ref "IC20") (pin "1") (pinfunction "PA00/SERCOM1_0/XIN32_1") (pintype "bidirectional"))
      (node (ref "X50") (pin "1") (pinfunction "1_1") (pintype "passive"))
    )
    (net (code "119") (name "Net-(IC20-PA01{slash}SERCOM1_1{slash}XOUT32)") (class "Default")
      (node (ref "C51") (pin "2") (pinfunction "2_2") (pintype "passive"))
      (node (ref "IC20") (pin "2") (pinfunction "PA01/SERCOM1_1/XOUT32_2") (pintype "bidirectional"))
      (node (ref "X50") (pin "2") (pinfunction "2_2") (pintype "passive"))
    )
    (net (code "120") (name "Net-(IC20-PA04{slash}SERCOM0_0)") (class "Default")
      (node (ref "IC20") (pin "13") (pinfunction "PA04/SERCOM0_0_13") (pintype "bidirectional"))
      (node (ref "R3") (pin "8") (pinfunction "2_8") (pintype "passive"))
    )
    (net (code "121") (name "Net-(IC20-PA05{slash}SERCOM0_1)") (class "Default")
      (node (ref "IC20") (pin "14") (pinfunction "PA05/SERCOM0_1_14") (pintype "bidirectional"))
      (node (ref "R3") (pin "7") (pinfunction "2_7") (pintype "passive"))
    )
    (net (code "122") (name "Net-(IC20-PA06{slash}SERCOM0_2)") (class "Default")
      (node (ref "IC20") (pin "15") (pinfunction "PA06/SERCOM0_2_15") (pintype "bidirectional"))
      (node (ref "R3") (pin "6") (pinfunction "2_6") (pintype "passive"))
    )
    (net (code "123") (name "Net-(IC20-PA08{slash}SERCOM0_0{slash}SERCOM2_0)") (class "Default")
      (node (ref "IC20") (pin "17") (pinfunction "PA08/SERCOM0_0/SERCOM2_0_17") (pintype "bidirectional"))
      (node (ref "IC20") (pin "35") (pinfunction "PA16/SERCOM1_0/SERCOM3_0\\_35") (pintype "bidirectional"))
      (node (ref "R2") (pin "8") (pinfunction "2_8") (pintype "passive"))
    )
    (net (code "124") (name "Net-(IC20-PA10{slash}SERCOM0_2{slash}SERCOM2_2)") (class "Default")
      (node (ref "IC20") (pin "19") (pinfunction "PA10/SERCOM0_2/SERCOM2_2_19") (pintype "bidirectional"))
      (node (ref "IC20") (pin "37") (pinfunction "PA18/SERCOM1_2/SERCOM3_2_37") (pintype "bidirectional"))
      (node (ref "R2") (pin "6") (pinfunction "2_6") (pintype "passive"))
    )
    (net (code "125") (name "Net-(IC20-PA11{slash}SERCOM0_3{slash}SERCOM2_3)") (class "Default")
      (node (ref "C5") (pin "2") (pinfunction "2_2") (pintype "passive"))
      (node (ref "IC20") (pin "20") (pinfunction "PA11/SERCOM0_3/SERCOM2_3_20") (pintype "bidirectional"))
    )
    (net (code "126") (name "Net-(IC20-PA21{slash}SERCOM5_3{slash}SERCOM3_3)") (class "Default")
      (node (ref "IC20") (pin "42") (pinfunction "PA21/SERCOM5_3/SERCOM3_3_42") (pintype "bidirectional"))
      (node (ref "R2") (pin "5") (pinfunction "2_5") (pintype "passive"))
    )
    (net (code "127") (name "Net-(IC20-PA22{slash}SERCOM3_0{slash}SERCOM5_0)") (class "Default")
      (node (ref "IC20") (pin "43") (pinfunction "PA22/SERCOM3_0/SERCOM5_0_43") (pintype "bidirectional"))
      (node (ref "R4") (pin "2") (pinfunction "1_2") (pintype "passive"))
    )
    (net (code "128") (name "Net-(IC20-PA23{slash}SERCOM3_1{slash}SERCOM5_1)") (class "Default")
      (node (ref "IC20") (pin "44") (pinfunction "PA23/SERCOM3_1/SERCOM5_1_44") (pintype "bidirectional"))
      (node (ref "R4") (pin "3") (pinfunction "1_3") (pintype "passive"))
    )
    (net (code "129") (name "Net-(IC20-PA24{slash}SERCOM3_2{slash}SERCOM5_2)") (class "Default")
      (node (ref "IC20") (pin "45") (pinfunction "PA24/SERCOM3_2/SERCOM5_2_45") (pintype "bidirectional"))
      (node (ref "R4") (pin "1") (pinfunction "1_1") (pintype "passive"))
    )
    (net (code "130") (name "Net-(IC20-PA25{slash}SERCOM3_3{slash}SERCOM5_3)") (class "Default")
      (node (ref "IC20") (pin "46") (pinfunction "PA25/SERCOM3_3/SERCOM5_3_46") (pintype "bidirectional"))
      (node (ref "R4") (pin "4") (pinfunction "1_4") (pintype "passive"))
    )
    (net (code "131") (name "Net-(IC20-PA27)") (class "Default")
      (node (ref "IC20") (pin "51") (pinfunction "PA27_51") (pintype "bidirectional"))
      (node (ref "TP6") (pin "TP") (pinfunction "TP_TP") (pintype "input"))
    )
    (net (code "132") (name "Net-(IC20-PA28)") (class "Default")
      (node (ref "IC20") (pin "53") (pinfunction "PA28_53") (pintype "bidirectional"))
      (node (ref "TP7") (pin "TP") (pinfunction "TP_TP") (pintype "input"))
    )
    (net (code "133") (name "Net-(IC20-VDDCORE)") (class "Default")
      (node (ref "C50") (pin "1") (pinfunction "1_1") (pintype "passive"))
      (node (ref "C54") (pin "1") (pinfunction "1_1") (pintype "passive"))
      (node (ref "IC20") (pin "55") (pinfunction "VDDCORE_55") (pintype "power_in"))
    )
    (net (code "134") (name "Net-(IC20-VDDIN)") (class "Default")
      (node (ref "C56") (pin "1") (pinfunction "1_1") (pintype "passive"))
      (node (ref "IC20") (pin "56") (pinfunction "VDDIN_56") (pintype "power_in"))
    )
    (net (code "135") (name "SWCLK") (class "Default")
      (node (ref "IC20") (pin "57") (pinfunction "PA30/SERCOM1_2/SWCLK_57") (pintype "bidirectional"))
      (node (ref "X1") (pin "4") (pinfunction "B_4") (pintype "passive"))
    )
    (net (code "136") (name "SWDIO") (class "Default")
      (node (ref "IC20") (pin "58") (pinfunction "PA31/SERCOM1_3/SWDIO_58") (pintype "bidirectional"))
      (node (ref "X1") (pin "2") (pinfunction "B_2") (pintype "passive"))
    )
    (net (code "137") (name "TCK") (class "Default")
      (node (ref "IC11") (pin "62") (pinfunction "TCK_62") (pintype "input"))
      (node (ref "IC20") (pin "49") (pinfunction "PB22/SERCOM5_2_49") (pintype "bidirectional"))
      (node (ref "JP1") (pin "TCK") (pinfunction "4_TCK") (pintype "passive"))
      (node (ref "TP4") (pin "TP") (pinfunction "TP_TP") (pintype "input"))
    )
    (net (code "138") (name "TDI") (class "Default")
      (node (ref "IC11") (pin "4") (pinfunction "TDI_4") (pintype "input"))
      (node (ref "IC20") (pin "3") (pinfunction "PA02_3") (pintype "bidirectional"))
      (node (ref "JP1") (pin "TDI") (pinfunction "2_TDI") (pintype "passive"))
      (node (ref "TP3") (pin "TP") (pinfunction "TP_TP") (pintype "input"))
    )
    (net (code "139") (name "TDO") (class "Default")
      (node (ref "IC11") (pin "73") (pinfunction "TDO_73") (pintype "output"))
      (node (ref "IC20") (pin "4") (pinfunction "PA03_4") (pintype "bidirectional"))
      (node (ref "JP1") (pin "TDO") (pinfunction "3_TDO") (pintype "passive"))
      (node (ref "TP2") (pin "TP") (pinfunction "TP_TP") (pintype "input"))
    )
    (net (code "140") (name "TMS") (class "Default")
      (node (ref "IC11") (pin "15") (pinfunction "TMS_15") (pintype "input"))
      (node (ref "IC20") (pin "50") (pinfunction "PB23/SERCOM5_3_50") (pintype "bidirectional"))
      (node (ref "JP1") (pin "TMS") (pinfunction "1_TMS") (pintype "passive"))
      (node (ref "R1") (pin "1") (pinfunction "1_1") (pintype "passive"))
      (node (ref "TP5") (pin "TP") (pinfunction "TP_TP") (pintype "input"))
    )
    (net (code "141") (name "VCC") (class "Default")
      (node (ref "C2") (pin "2") (pinfunction "2_2") (pintype "passive"))
      (node (ref "C4") (pin "1") (pinfunction "1_1") (pintype "passive"))
      (node (ref "C53") (pin "2") (pinfunction "2_2") (pintype "passive"))
      (node (ref "C55") (pin "1") (pinfunction "1_1") (pintype "passive"))
      (node (ref "C57") (pin "1") (pinfunction "1_1") (pintype "passive"))
      (node (ref "C58") (pin "1") (pinfunction "1_1") (pintype "passive"))
      (node (ref "C59") (pin "1") (pinfunction "1_1") (pintype "passive"))
      (node (ref "C60") (pin "2") (pinfunction "2_2") (pintype "passive"))
      (node (ref "C80") (pin "2") (pinfunction "2_2") (pintype "passive"))
      (node (ref "C81") (pin "2") (pinfunction "2_2") (pintype "passive"))
      (node (ref "IC1") (pin "6") (pinfunction "VCCB_6") (pintype "power_in"))
      (node (ref "IC10") (pin "6") (pinfunction "VCCB_6") (pintype "power_in"))
      (node (ref "IC12") (pin "6") (pinfunction "VCCB_6") (pintype "power_in"))
      (node (ref "IC13") (pin "6") (pinfunction "VCCB_6") (pintype "power_in"))
      (node (ref "IC14") (pin "6") (pinfunction "VCCB_6") (pintype "power_in"))
      (node (ref "IC15") (pin "1") (pinfunction "VIN_1") (pintype "power_in"))
      (node (ref "IC15") (pin "3") (pinfunction "EN_3") (pintype "input"))
      (node (ref "IC16") (pin "6") (pinfunction "VCCB_6") (pintype "power_in"))
      (node (ref "IC17") (pin "6") (pinfunction "VCCB_6") (pintype "power_in"))
      (node (ref "IC18") (pin "6") (pinfunction "VCCB_6") (pintype "power_in"))
      (node (ref "IC19") (pin "6") (pinfunction "VCCB_6") (pintype "power_in"))
      (node (ref "IC2") (pin "6") (pinfunction "VCCB_6") (pintype "power_in"))
      (node (ref "IC20") (pin "21") (pinfunction "VDDIO_21") (pintype "power_in"))
      (node (ref "IC20") (pin "34") (pinfunction "VDDIO_34") (pintype "power_in"))
      (node (ref "IC20") (pin "48") (pinfunction "VDDIO_48") (pintype "power_in"))
      (node (ref "IC20") (pin "8") (pinfunction "VDDANA_8") (pintype "power_in"))
      (node (ref "IC21") (pin "28") (pinfunction "VCC_28") (pintype "power_in"))
      (node (ref "IC3") (pin "6") (pinfunction "VCCB_6") (pintype "power_in"))
      (node (ref "IC4") (pin "6") (pinfunction "VCCB_6") (pintype "power_in"))
      (node (ref "IC5") (pin "6") (pinfunction "VCCB_6") (pintype "power_in"))
      (node (ref "IC6") (pin "6") (pinfunction "VCCB_6") (pintype "power_in"))
      (node (ref "IC7") (pin "6") (pinfunction "VCCB_6") (pintype "power_in"))
      (node (ref "IC8") (pin "6") (pinfunction "VCCB_6") (pintype "power_in"))
      (node (ref "IC9") (pin "64") (pinfunction "VCC_64") (pintype "power_in"))
      (node (ref "TP1") (pin "TP") (pinfunction "TP_TP") (pintype "input"))
      (node (ref "U1") (pin "64") (pinfunction "VCC_64") (pintype "bidirectional"))
      (node (ref "X1") (pin "1") (pinfunction "B_1") (pintype "passive"))
      (node (ref "X2") (pin "1") (pinfunction "1_1") (pintype "passive"))
    )
    (net (code "142") (name "VCC_CPLD") (class "Default")
      (node (ref "C1") (pin "2") (pinfunction "2_2") (pintype "passive"))
      (node (ref "C3") (pin "1") (pinfunction "1_1") (pintype "passive"))
      (node (ref "C61") (pin "2") (pinfunction "2_2") (pintype "passive"))
      (node (ref "C62") (pin "2") (pinfunction "2_2") (pintype "passive"))
      (node (ref "C63") (pin "2") (pinfunction "2_2") (pintype "passive"))
      (node (ref "C64") (pin "2") (pinfunction "2_2") (pintype "passive"))
      (node (ref "C65") (pin "2") (pinfunction "2_2") (pintype "passive"))
      (node (ref "C66") (pin "2") (pinfunction "2_2") (pintype "passive"))
      (node (ref "C67") (pin "2") (pinfunction "2_2") (pintype "passive"))
      (node (ref "C68") (pin "2") (pinfunction "2_2") (pintype "passive"))
      (node (ref "C71") (pin "2") (pinfunction "2_2") (pintype "passive"))
      (node (ref "C72") (pin "2") (pinfunction "2_2") (pintype "passive"))
      (node (ref "C73") (pin "2") (pinfunction "2_2") (pintype "passive"))
      (node (ref "C74") (pin "2") (pinfunction "2_2") (pintype "passive"))
      (node (ref "C75") (pin "2") (pinfunction "2_2") (pintype "passive"))
      (node (ref "C76") (pin "2") (pinfunction "2_2") (pintype "passive"))
      (node (ref "C77") (pin "2") (pinfunction "2_2") (pintype "passive"))
      (node (ref "C78") (pin "2") (pinfunction "2_2") (pintype "passive"))
      (node (ref "C79") (pin "2") (pinfunction "2_2") (pintype "passive"))
      (node (ref "IC1") (pin "1") (pinfunction "VCCA_1") (pintype "power_in"))
      (node (ref "IC10") (pin "1") (pinfunction "VCCA_1") (pintype "power_in"))
      (node (ref "IC11") (pin "18") (pinfunction "VCC_3V3_18") (pintype "power_in"))
      (node (ref "IC11") (pin "3") (pinfunction "VCC_3V3_3") (pintype "power_in"))
      (node (ref "IC11") (pin "34") (pinfunction "VCC_3V3_34") (pintype "power_in"))
      (node (ref "IC11") (pin "39") (pinfunction "VCC_3V3_39") (pintype "power_in"))
      (node (ref "IC11") (pin "51") (pinfunction "VCC_3V3_51") (pintype "power_in"))
      (node (ref "IC11") (pin "66") (pinfunction "VCC_3V3_66") (pintype "power_in"))
      (node (ref "IC11") (pin "82") (pinfunction "VCC_3V3_82") (pintype "power_in"))
      (node (ref "IC11") (pin "91") (pinfunction "VCC_3V3_91") (pintype "power_in"))
      (node (ref "IC12") (pin "1") (pinfunction "VCCA_1") (pintype "power_in"))
      (node (ref "IC13") (pin "1") (pinfunction "VCCA_1") (pintype "power_in"))
      (node (ref "IC14") (pin "1") (pinfunction "VCCA_1") (pintype "power_in"))
      (node (ref "IC15") (pin "5") (pinfunction "VOUT_5") (pintype "power_in"))
      (node (ref "IC16") (pin "1") (pinfunction "VCCA_1") (pintype "power_in"))
      (node (ref "IC17") (pin "1") (pinfunction "VCCA_1") (pintype "power_in"))
      (node (ref "IC18") (pin "1") (pinfunction "VCCA_1") (pintype "power_in"))
      (node (ref "IC19") (pin "1") (pinfunction "VCCA_1") (pintype "power_in"))
      (node (ref "IC2") (pin "1") (pinfunction "VCCA_1") (pintype "power_in"))
      (node (ref "IC3") (pin "1") (pinfunction "VCCA_1") (pintype "power_in"))
      (node (ref "IC4") (pin "1") (pinfunction "VCCA_1") (pintype "power_in"))
      (node (ref "IC5") (pin "1") (pinfunction "VCCA_1") (pintype "power_in"))
      (node (ref "IC6") (pin "1") (pinfunction "VCCA_1") (pintype "power_in"))
      (node (ref "IC7") (pin "1") (pinfunction "VCCA_1") (pintype "power_in"))
      (node (ref "IC8") (pin "1") (pinfunction "VCCA_1") (pintype "power_in"))
      (node (ref "JP1") (pin "VCC") (pinfunction "6_VCC") (pintype "passive"))
      (node (ref "R1") (pin "2") (pinfunction "2_2") (pintype "passive"))
    )
    (net (code "143") (name "X_ADR") (class "Default")
      (node (ref "IC11") (pin "53") (pinfunction "P53_53") (pintype "bidirectional"))
      (node (ref "IC20") (pin "59") (pinfunction "PB30/SERCOM5_0_59") (pintype "bidirectional"))
    )
    (net (code "144") (name "X_SCLK") (class "Default")
      (node (ref "R4") (pin "6") (pinfunction "2_6") (pintype "passive"))
      (node (ref "X2") (pin "3") (pinfunction "3_3") (pintype "passive"))
    )
    (net (code "145") (name "X_SRX") (class "Default")
      (node (ref "R4") (pin "8") (pinfunction "2_8") (pintype "passive"))
      (node (ref "X2") (pin "5") (pinfunction "5_5") (pintype "passive"))
    )
    (net (code "146") (name "X_STX") (class "Default")
      (node (ref "R4") (pin "7") (pinfunction "2_7") (pintype "passive"))
      (node (ref "X2") (pin "4") (pinfunction "4_4") (pintype "passive"))
    )
    (net (code "147") (name "unconnected-(IC20-PA15{slash}SERCOM2_3{slash}SERCOM4_3{slash}XOUT-Pad32)") (class "Default")
      (node (ref "IC20") (pin "32") (pinfunction "PA15/SERCOM2_3/SERCOM4_3/XOUT_32") (pintype "bidirectional"))
    )
    (net (code "148") (name "unconnected-(R3D-1-Pad4)") (class "Default")
      (node (ref "R3") (pin "4") (pinfunction "1_4") (pintype "passive"))
    )
    (net (code "149") (name "unconnected-(R3D-2-Pad5)") (class "Default")
      (node (ref "R3") (pin "5") (pinfunction "2_5") (pintype "passive"))
    )
    (net (code "150") (name "unconnected-(U1-I{slash}~{E}-Pad12)") (class "Default")
      (node (ref "U1") (pin "12") (pinfunction "I/~{E}_12") (pintype "bidirectional"))
    )
    (net (code "151") (name "unconnected-(U1-XIN-Pad6)") (class "Default")
      (node (ref "U1") (pin "6") (pinfunction "XIN_6") (pintype "bidirectional"))
    )
    (net (code "152") (name "unconnected-(U1-XOUT-Pad7)") (class "Default")
      (node (ref "U1") (pin "7") (pinfunction "XOUT_7") (pintype "bidirectional"))
    )
    (net (code "153") (name "unconnected-(X1G-B-Pad6)") (class "Default")
      (node (ref "X1") (pin "6") (pinfunction "B_6") (pintype "passive"))
    )
    (net (code "154") (name "unconnected-(X1H-B-Pad7)") (class "Default")
      (node (ref "X1") (pin "7") (pinfunction "B_7") (pintype "passive"))
    )
    (net (code "155") (name "unconnected-(X1I-B-Pad8)") (class "Default")
      (node (ref "X1") (pin "8") (pinfunction "B_8") (pintype "passive"))
    )
    (net (code "156") (name "~{D_HALT}") (class "Default")
      (node (ref "IC20") (pin "41") (pinfunction "PA20/SERCOM5_2/SERCOM3_2_41") (pintype "bidirectional"))
      (node (ref "IC9") (pin "51") (pinfunction "~{HALT}_51") (pintype "input"))
      (node (ref "U1") (pin "51") (pinfunction "~{HALT}_51") (pintype "bidirectional"))
    )
    (net (code "157") (name "~{D_INIT}") (class "Default")
      (node (ref "IC11") (pin "81") (pinfunction "P81_81") (pintype "bidirectional"))
      (node (ref "IC9") (pin "52") (pinfunction "~{INIT}_52") (pintype "input"))
    )
    (net (code "158") (name "~{D_IRL}") (class "Default")
      (node (ref "IC9") (pin "5") (pinfunction "IRL_5") (pintype "bidirectional"))
      (node (ref "U1") (pin "5") (pinfunction "IRL_5") (pintype "bidirectional"))
    )
    (net (code "159") (name "~{D_IRP}") (class "Default")
      (node (ref "IC11") (pin "55") (pinfunction "P55_55") (pintype "bidirectional"))
      (node (ref "IC9") (pin "4") (pinfunction "IRP_4") (pintype "bidirectional"))
      (node (ref "U1") (pin "4") (pinfunction "IRP_4") (pintype "bidirectional"))
    )
    (net (code "160") (name "~{D_NMI}") (class "Default")
      (node (ref "IC9") (pin "3") (pinfunction "~{NMI}_3") (pintype "input"))
      (node (ref "U1") (pin "3") (pinfunction "~{NMI}_3") (pintype "bidirectional"))
    )
    (net (code "161") (name "~{D_RD}") (class "Default")
      (node (ref "IC11") (pin "83") (pinfunction "P83_83") (pintype "bidirectional"))
      (node (ref "IC9") (pin "10") (pinfunction "IS/~{RD}_10") (pintype "output"))
    )
    (net (code "162") (name "~{D_TEST}") (class "Default")
      (node (ref "IC9") (pin "49") (pinfunction "~{TEST}_49") (pintype "input"))
      (node (ref "U1") (pin "49") (pinfunction "~{TEST}_49") (pintype "bidirectional"))
    )
    (net (code "163") (name "~{D_WDC}") (class "Default")
      (node (ref "IC9") (pin "53") (pinfunction "~{WDC}_53") (pintype "output"))
      (node (ref "U1") (pin "53") (pinfunction "WDC_53") (pintype "bidirectional"))
    )
    (net (code "164") (name "~{D_WI}") (class "Default")
      (node (ref "IC9") (pin "50") (pinfunction "~{WI}_50") (pintype "input"))
      (node (ref "U1") (pin "50") (pinfunction "~{WI}_50") (pintype "bidirectional"))
    )
    (net (code "165") (name "~{D_WR}") (class "Default")
      (node (ref "IC11") (pin "89") (pinfunction "P89/GCLK1_89") (pintype "input"))
      (node (ref "IC9") (pin "11") (pinfunction "OS/~{WR}_11") (pintype "output"))
    )
    (net (code "166") (name "~{E_INIT}") (class "Default")
      (node (ref "IC11") (pin "98") (pinfunction "P98_98") (pintype "bidirectional"))
      (node (ref "U1") (pin "52") (pinfunction "~{INIT}_52") (pintype "bidirectional"))
    )
    (net (code "167") (name "~{E_IS}") (class "Default")
      (node (ref "IC11") (pin "54") (pinfunction "P54_54") (pintype "bidirectional"))
      (node (ref "U1") (pin "10") (pinfunction "IS/~{RD}_10") (pintype "bidirectional"))
    )
    (net (code "168") (name "~{E_OS}") (class "Default")
      (node (ref "IC11") (pin "65") (pinfunction "P65_65") (pintype "bidirectional"))
      (node (ref "U1") (pin "11") (pinfunction "OS/~{WR}_11") (pintype "bidirectional"))
    )
    (net (code "169") (name "~{M_RAM_CS}") (class "Default")
      (node (ref "IC11") (pin "22") (pinfunction "P22_22") (pintype "bidirectional"))
      (node (ref "IC20") (pin "60") (pinfunction "PB31/SERCOM5_1_60") (pintype "bidirectional"))
      (node (ref "IC21") (pin "20") (pinfunction "~{CE}_20") (pintype "input"))
    )
    (net (code "170") (name "~{M_RD}") (class "Default")
      (node (ref "IC11") (pin "14") (pinfunction "P14_14") (pintype "bidirectional"))
      (node (ref "IC21") (pin "22") (pinfunction "~{OE}_22") (pintype "input"))
    )
    (net (code "171") (name "~{M_WR}") (class "Default")
      (node (ref "IC11") (pin "19") (pinfunction "P19_19") (pintype "bidirectional"))
      (node (ref "IC21") (pin "27") (pinfunction "~{WE}_27") (pintype "input"))
    )
    (net (code "172") (name "~{RESET}") (class "Default")
      (node (ref "IC20") (pin "52") (pinfunction "~{RESET}_52") (pintype "input"))
      (node (ref "X1") (pin "10") (pinfunction "B_10") (pintype "passive"))
    )
    (net (code "173") (name "~{X_INIT}") (class "Default")
      (node (ref "IC11") (pin "97") (pinfunction "P97_97") (pintype "bidirectional"))
      (node (ref "IC20") (pin "16") (pinfunction "PA07/SERCOM0_3_16") (pintype "bidirectional"))
    )
    (net (code "174") (name "~{X_INT}") (class "Default")
      (node (ref "R4") (pin "5") (pinfunction "2_5") (pintype "passive"))
      (node (ref "X2") (pin "2") (pinfunction "2_2") (pintype "passive"))
    )
    (net (code "175") (name "~{X_RD}") (class "Default")
      (node (ref "IC11") (pin "9") (pinfunction "P9_9") (pintype "bidirectional"))
      (node (ref "IC20") (pin "39") (pinfunction "PB16/SERCOM5_0_39") (pintype "bidirectional"))
    )
    (net (code "176") (name "~{X_WR}") (class "Default")
      (node (ref "IC11") (pin "13") (pinfunction "P13_13") (pintype "bidirectional"))
      (node (ref "IC20") (pin "40") (pinfunction "PB17/SERCOM5_1_40") (pintype "bidirectional"))
    )
  )
)
